# LDOs.net
KiCad netlist of a schematic drawn in Altium Designer
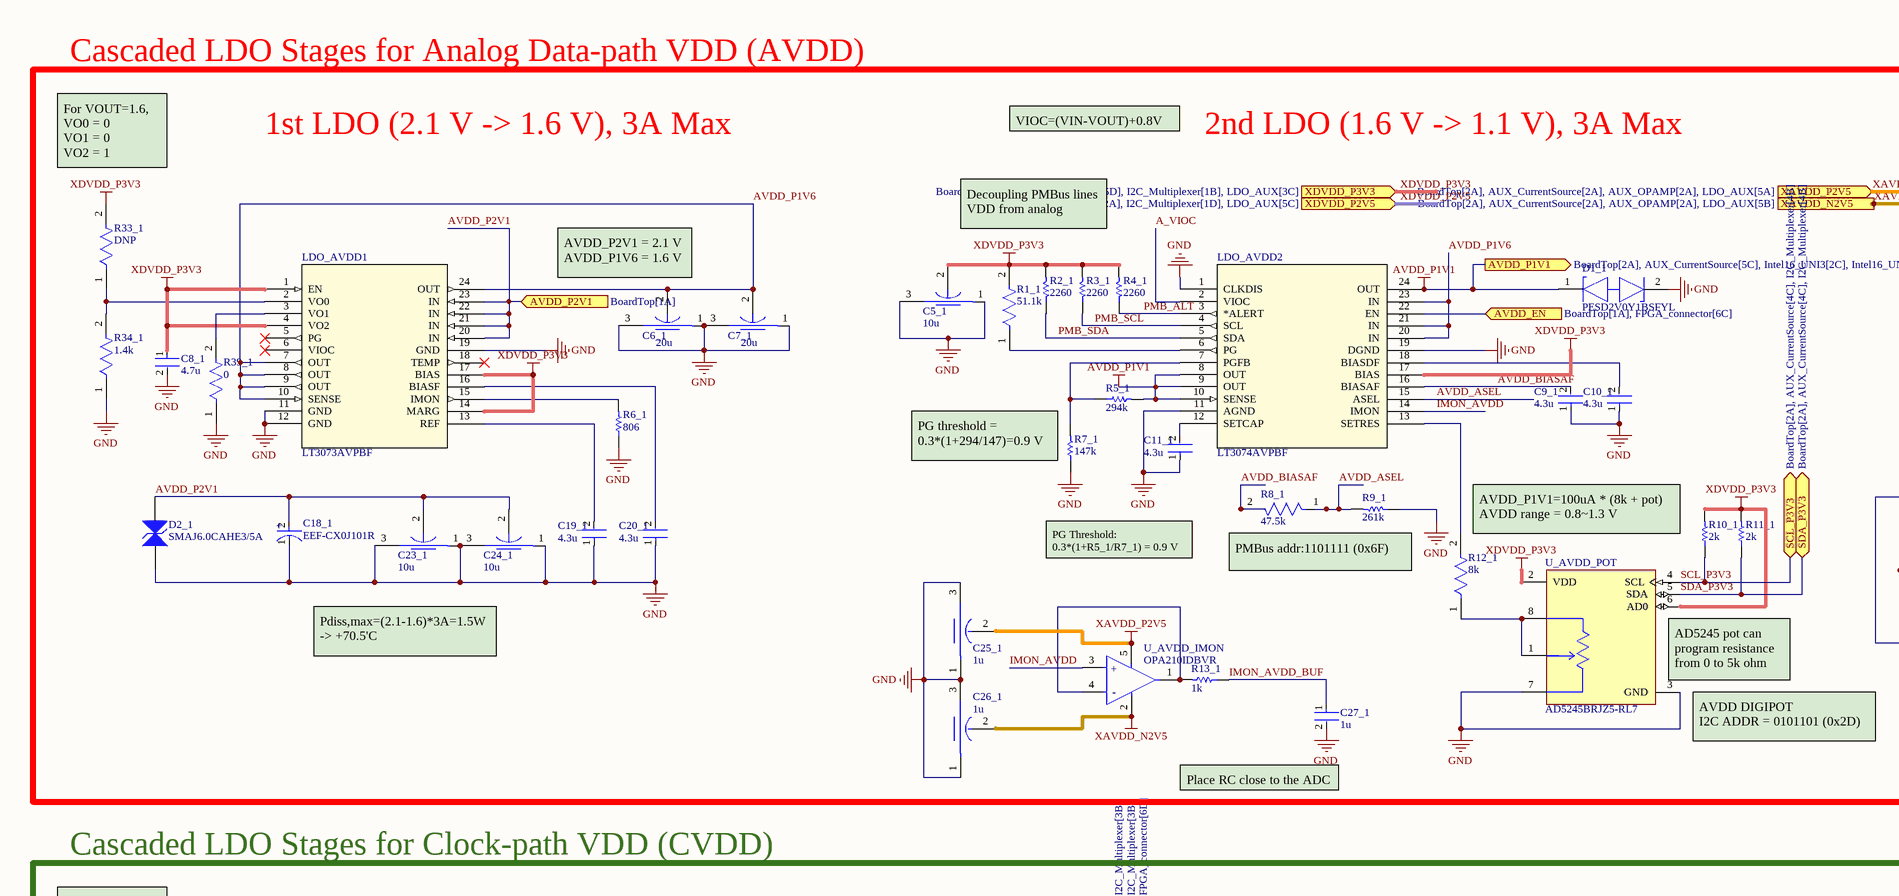
[diagram p0: LDOs.SchDoc, top left]
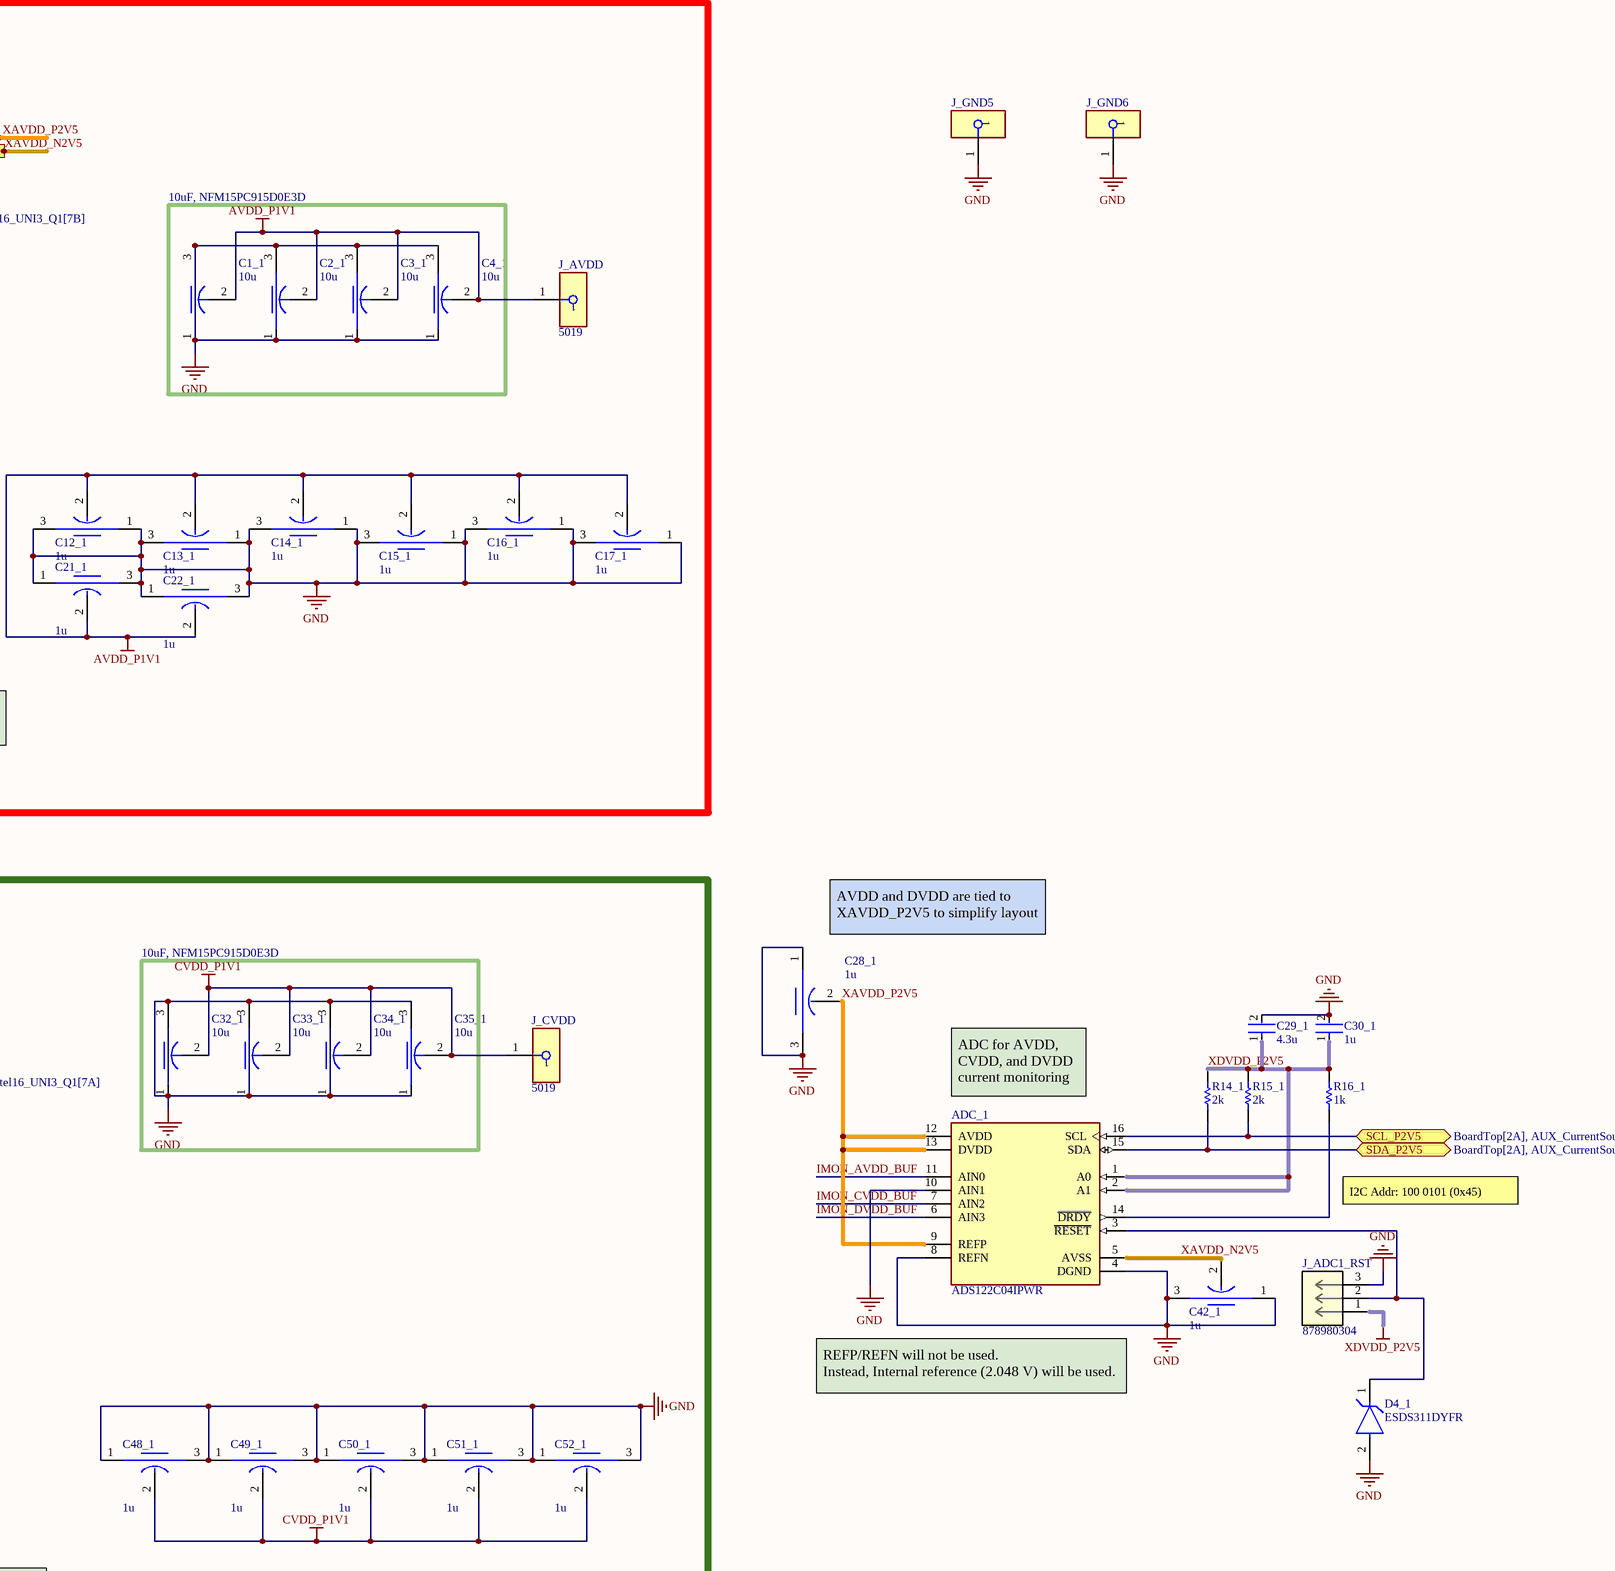
[diagram p1: LDOs.SchDoc, top right]
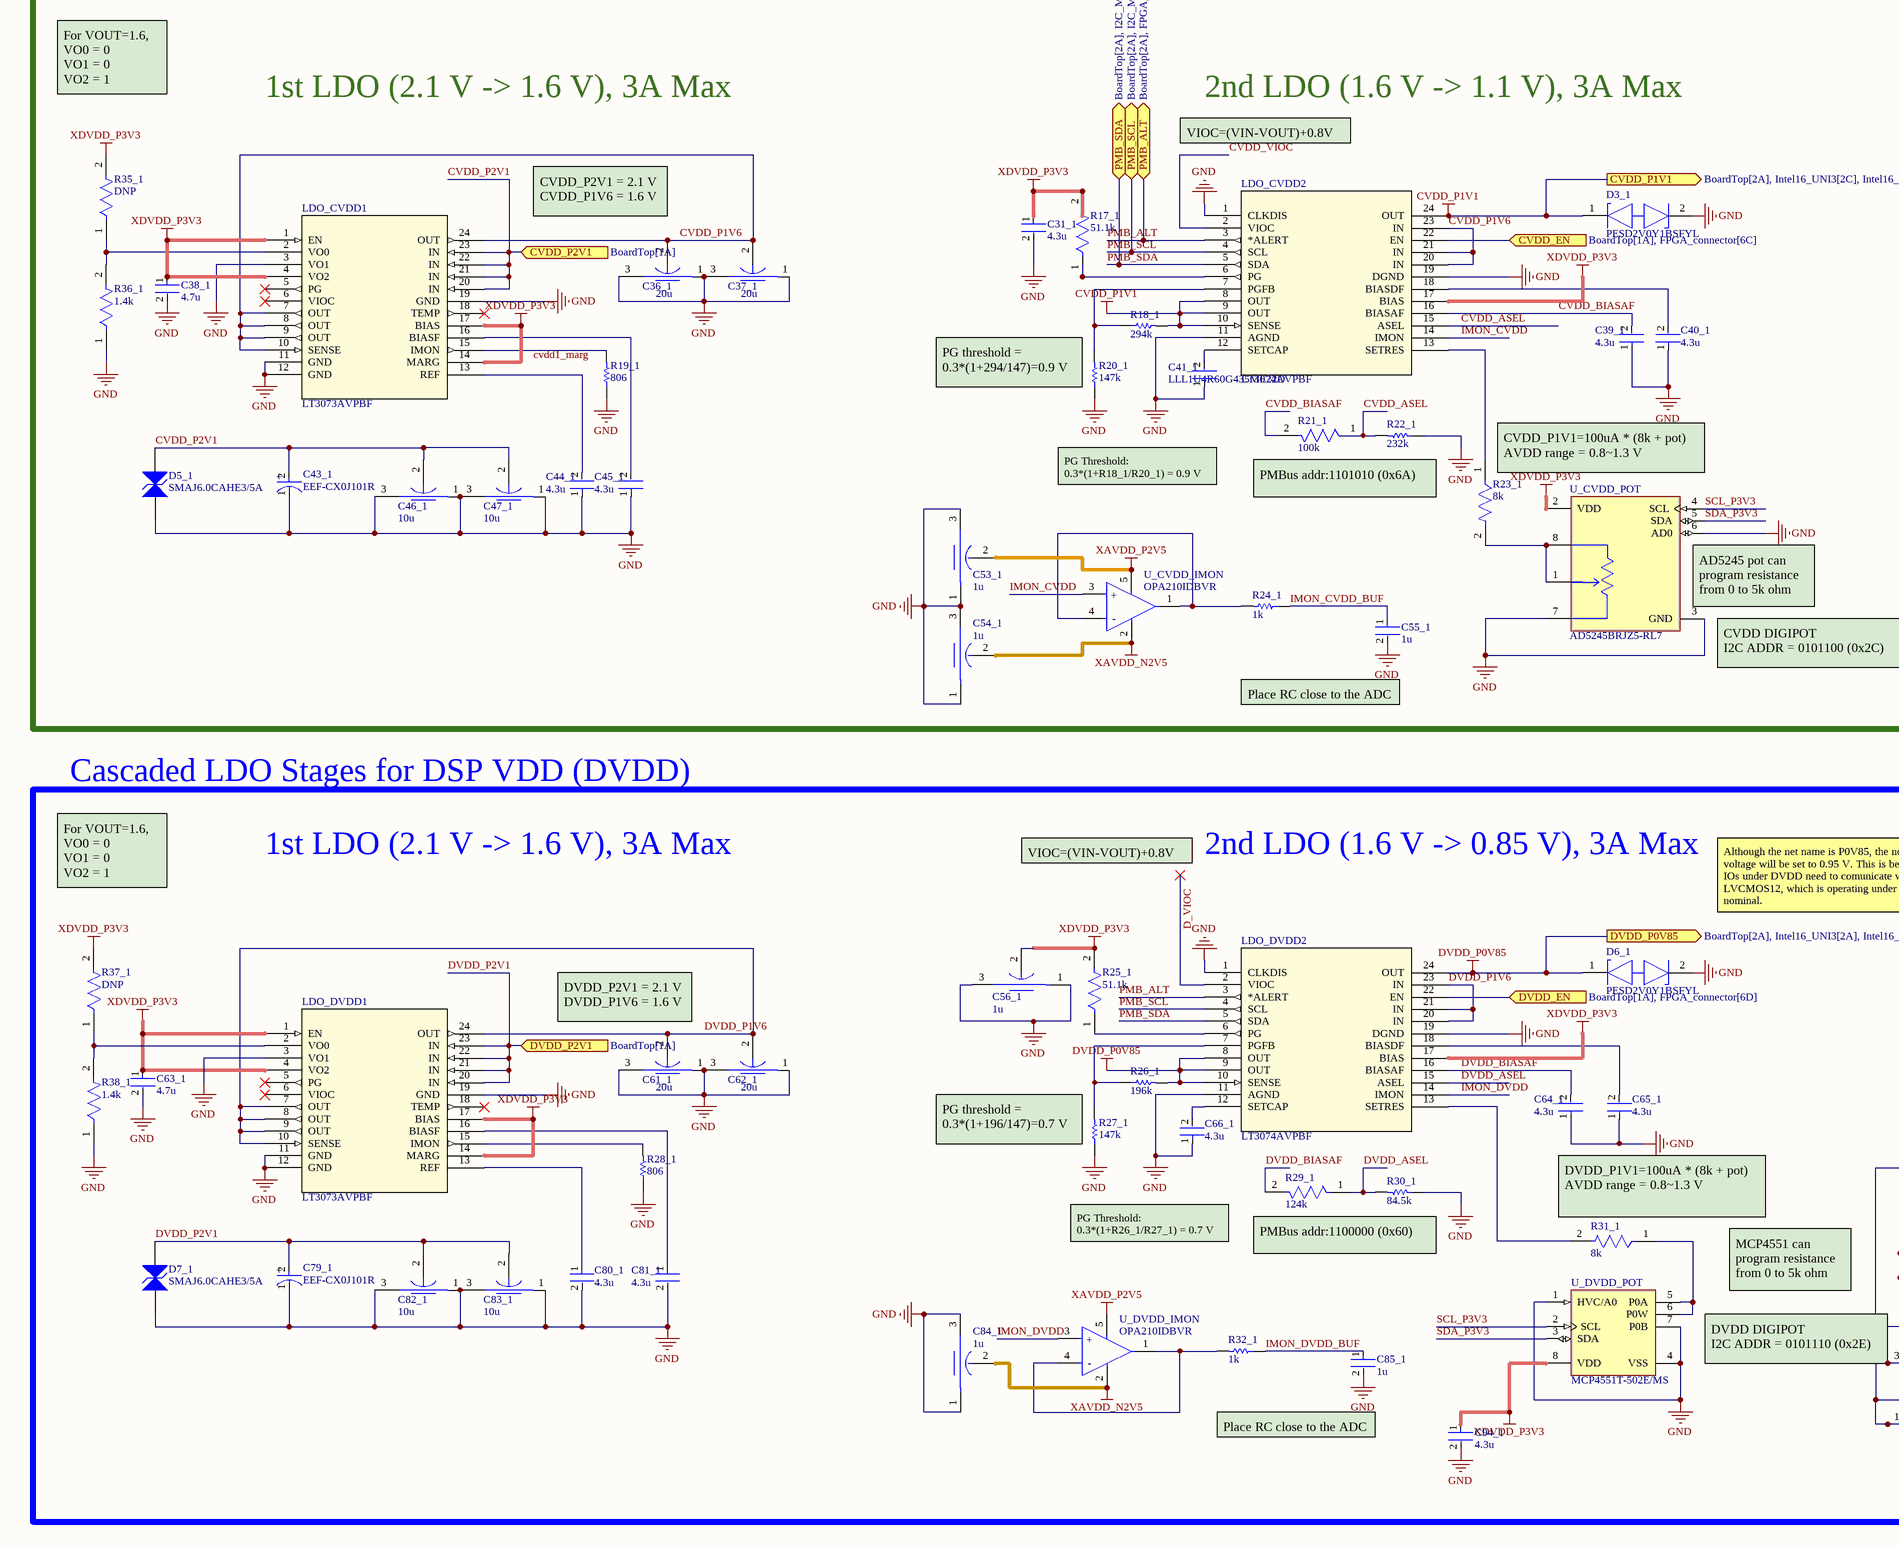
[diagram p2: LDOs.SchDoc, bottom left]
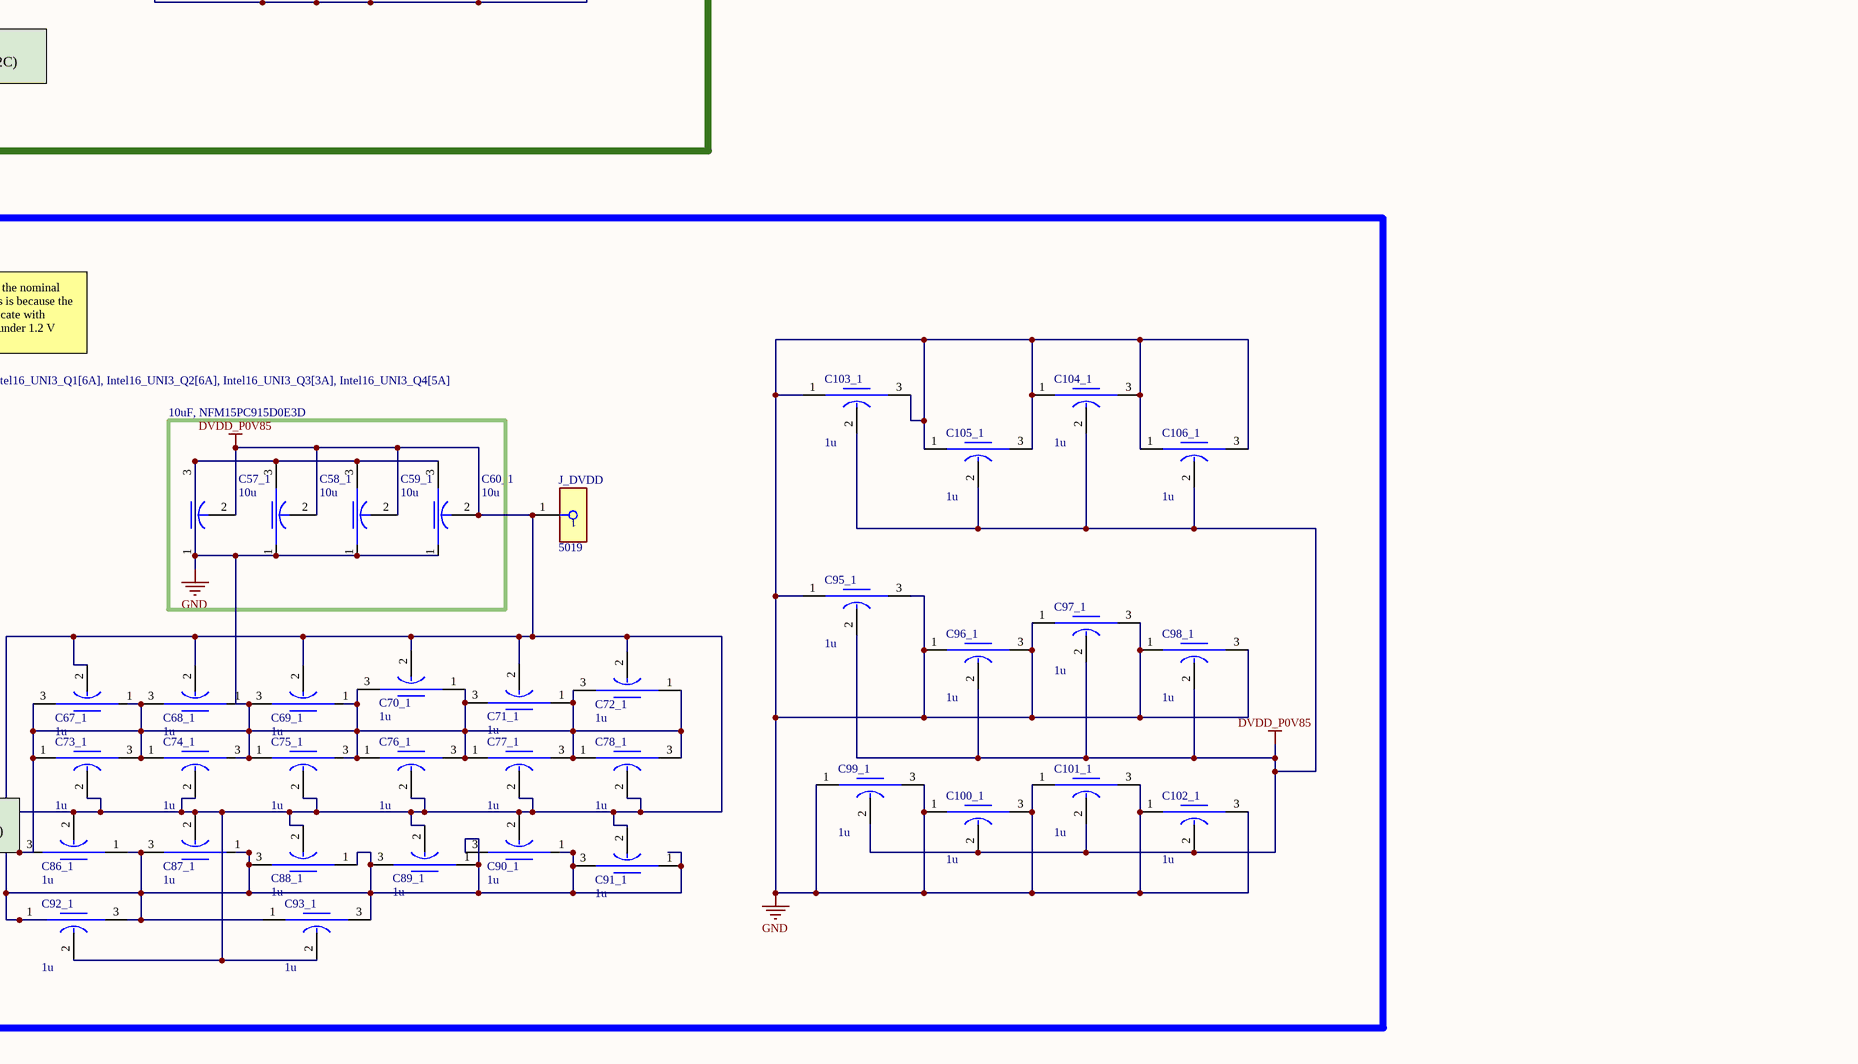
[diagram p3: LDOs.SchDoc, bottom right]

(export (version "E")
  (design (tool "Eeschema 10.0.6"))
  (components
    (comp (ref "ADC_1")
      (value "ADS122C04IPWR")
      (footprint "FP-PW0016A-IPC_C")
      (description "IC ADC 24BIT SIGMA-DELTA 16TSSOP")
      (libsource (lib "Altium Content Vault") (part "c28109da439a1fe3ed8269d84f6cd58"))
    )
    (comp (ref "C1_1")
      (value "10u")
      (footprint "FP-NFM15-0_2-MFG")
      (description "CAP FEEDTHRU")
      (libsource (lib "Altium Content Vault") (part "0d6e7657c98936515f4dd3c3b322889"))
    )
    (comp (ref "C2_1")
      (value "10u")
      (footprint "FP-NFM15-0_2-MFG")
      (description "CAP FEEDTHRU")
      (libsource (lib "Altium Content Vault") (part "0d6e7657c98936515f4dd3c3b322889"))
    )
    (comp (ref "C3_1")
      (value "10u")
      (footprint "FP-NFM15-0_2-MFG")
      (description "CAP FEEDTHRU")
      (libsource (lib "Altium Content Vault") (part "0d6e7657c98936515f4dd3c3b322889"))
    )
    (comp (ref "C4_1")
      (value "10u")
      (footprint "FP-NFM15-0_2-MFG")
      (description "CAP FEEDTHRU")
      (libsource (lib "Altium Content Vault") (part "0d6e7657c98936515f4dd3c3b322889"))
    )
    (comp (ref "C5_1")
      (value "10u")
      (footprint "FP-NFM15-0_2-MFG")
      (description "CAP FEEDTHRU")
      (libsource (lib "Altium Content Vault") (part "0d6e7657c98936515f4dd3c3b322889"))
    )
    (comp (ref "C6_1")
      (value "20u")
      (footprint "FP-NFM15-0_2-MFG")
      (description "CAP FEEDTHRU")
      (libsource (lib "Altium Content Vault") (part "0d6e7657c98936515f4dd3c3b322889"))
    )
    (comp (ref "C7_1")
      (value "20u")
      (footprint "FP-NFM15-0_2-MFG")
      (description "CAP FEEDTHRU")
      (libsource (lib "Altium Content Vault") (part "0d6e7657c98936515f4dd3c3b322889"))
    )
    (comp (ref "C8_1")
      (value "4.7u")
      (footprint "FP-GRM155-0_1-IPC_B")
      (description "Chip Multilayer Ceramic Capacitors for General Purpose, 0402, 4.7uF, X5R, 15%, 20%, 6.3V")
      (fields (field (name "VOLTAGE") "6.3V") (field (name "TOLERANCE") "20%"))
      (libsource (lib "Altium Content Vault") (part "11868f565c42a9108669ba33697ecf6"))
    )
    (comp (ref "C9_1")
      (value "4.3u")
      (footprint "FP-LLL1U4-0_05-IPC_C")
      (description "Cap Ceramic Monolithic 4.3uF 20% 4V X5R 15% 02404 (0610M)")
      (fields (field (name "TOLERANCE") "20%"))
      (libsource (lib "LLL_cap") (part "CMP-06035-061933-1"))
    )
    (comp (ref "C10_1")
      (value "4.3u")
      (footprint "FP-LLL1U4-0_05-IPC_C")
      (description "Cap Ceramic Monolithic 4.3uF 20% 4V X5R 15% 02404 (0610M)")
      (fields (field (name "TOLERANCE") "20%"))
      (libsource (lib "LLL_cap") (part "CMP-06035-061933-1"))
    )
    (comp (ref "C11_1")
      (value "4.3u")
      (footprint "FP-LLL1U4-0_05-IPC_C")
      (description "Cap Ceramic Monolithic 4.3uF 20% 4V X5R 15% 02404 (0610M)")
      (fields (field (name "TOLERANCE") "20%"))
      (libsource (lib "LLL_cap") (part "CMP-06035-061933-1"))
    )
    (comp (ref "C12_1")
      (value "1u")
      (footprint "PCBComponent_1")
      (description "0402(1005M) 4V 1.0UF +/- 20% 3 T")
      (fields (field (name "TOLERANCE") "20%"))
      (libsource (lib "NFM15HC105D0G3D") (part "CMP-06053-000757-1"))
    )
    (comp (ref "C13_1")
      (value "1u")
      (footprint "PCBComponent_1")
      (description "0402(1005M) 4V 1.0UF +/- 20% 3 T")
      (fields (field (name "TOLERANCE") "20%"))
      (libsource (lib "NFM15HC105D0G3D") (part "CMP-06053-000757-1"))
    )
    (comp (ref "C14_1")
      (value "1u")
      (footprint "PCBComponent_1")
      (description "0402(1005M) 4V 1.0UF +/- 20% 3 T")
      (fields (field (name "TOLERANCE") "20%"))
      (libsource (lib "NFM15HC105D0G3D") (part "CMP-06053-000757-1"))
    )
    (comp (ref "C15_1")
      (value "1u")
      (footprint "PCBComponent_1")
      (description "0402(1005M) 4V 1.0UF +/- 20% 3 T")
      (fields (field (name "TOLERANCE") "20%"))
      (libsource (lib "NFM15HC105D0G3D") (part "CMP-06053-000757-1"))
    )
    (comp (ref "C16_1")
      (value "1u")
      (footprint "PCBComponent_1")
      (description "0402(1005M) 4V 1.0UF +/- 20% 3 T")
      (fields (field (name "TOLERANCE") "20%"))
      (libsource (lib "NFM15HC105D0G3D") (part "CMP-06053-000757-1"))
    )
    (comp (ref "C17_1")
      (value "1u")
      (footprint "PCBComponent_1")
      (description "0402(1005M) 4V 1.0UF +/- 20% 3 T")
      (fields (field (name "TOLERANCE") "20%"))
      (libsource (lib "NFM15HC105D0G3D") (part "CMP-06053-000757-1"))
    )
    (comp (ref "C18_1")
      (value "EEF-CX0J101R")
      (footprint "FP-CX-MFG")
      (description "CAP ALUM POLY 100UF 20% 6.3V SMD")
      (fields (field (name "VOLTAGE") "6.3V") (field (name "TOLERANCE") "20%"))
      (libsource (lib "Altium Content Vault") (part "a00bbbee19879c290e62620ae7e47b1"))
    )
    (comp (ref "C19_1")
      (value "4.3u")
      (footprint "FP-LLL1U4-0_05-IPC_C")
      (description "Cap Ceramic Monolithic 4.3uF 20% 4V X5R 15% 02404 (0610M)")
      (fields (field (name "TOLERANCE") "20%"))
      (libsource (lib "LLL_cap") (part "CMP-06035-061933-1"))
    )
    (comp (ref "C20_1")
      (value "4.3u")
      (footprint "FP-LLL1U4-0_05-IPC_C")
      (description "Cap Ceramic Monolithic 4.3uF 20% 4V X5R 15% 02404 (0610M)")
      (fields (field (name "TOLERANCE") "20%"))
      (libsource (lib "LLL_cap") (part "CMP-06035-061933-1"))
    )
    (comp (ref "C21_1")
      (value "1u")
      (footprint "PCBComponent_1")
      (description "0402(1005M) 4V 1.0UF +/- 20% 3 T")
      (fields (field (name "TOLERANCE") "20%"))
      (libsource (lib "NFM15HC105D0G3D") (part "CMP-06053-000757-1"))
    )
    (comp (ref "C22_1")
      (value "1u")
      (footprint "PCBComponent_1")
      (description "0402(1005M) 4V 1.0UF +/- 20% 3 T")
      (fields (field (name "TOLERANCE") "20%"))
      (libsource (lib "NFM15HC105D0G3D") (part "CMP-06053-000757-1"))
    )
    (comp (ref "C23_1")
      (value "10u")
      (footprint "FP-NFM15-0_2-MFG")
      (description "CAP FEEDTHRU")
      (libsource (lib "Altium Content Vault") (part "0d6e7657c98936515f4dd3c3b322889"))
    )
    (comp (ref "C24_1")
      (value "10u")
      (footprint "FP-NFM15-0_2-MFG")
      (description "CAP FEEDTHRU")
      (libsource (lib "Altium Content Vault") (part "0d6e7657c98936515f4dd3c3b322889"))
    )
    (comp (ref "C25_1")
      (value "1u")
      (footprint "PCBComponent_1")
      (description "0402(1005M) 4V 1.0UF +/- 20% 3 T")
      (fields (field (name "TOLERANCE") "20%"))
      (libsource (lib "NFM15HC105D0G3D") (part "CMP-06053-000757-1"))
    )
    (comp (ref "C26_1")
      (value "1u")
      (footprint "PCBComponent_1")
      (description "0402(1005M) 4V 1.0UF +/- 20% 3 T")
      (fields (field (name "TOLERANCE") "20%"))
      (libsource (lib "NFM15HC105D0G3D") (part "CMP-06053-000757-1"))
    )
    (comp (ref "C27_1")
      (value "1u")
      (footprint "FP-C0402C105K8PACTU-IPC_A")
      (description "CAP CER 1UF 10V X5R 0402")
      (fields (field (name "VOLTAGE") "10V") (field (name "TOLERANCE") "10%"))
      (libsource (lib "KEMET_1uF_0402_cap") (part "CMP-2008-02081-2"))
    )
    (comp (ref "C28_1")
      (value "1u")
      (footprint "PCBComponent_1")
      (description "0402(1005M) 4V 1.0UF +/- 20% 3 T")
      (fields (field (name "TOLERANCE") "20%"))
      (libsource (lib "NFM15HC105D0G3D") (part "CMP-06053-000757-1"))
    )
    (comp (ref "C29_1")
      (value "4.3u")
      (footprint "FP-LLL1U4-0_05-MFG")
      (description "Cap Ceramic Monolithic 4.3uF 20% 4V X5R 15% 02404 (0610M)")
      (fields (field (name "TOLERANCE") "20%"))
      (libsource (lib "Altium Content Vault") (part "b4654b650e69147ec39a6b967a45e02"))
    )
    (comp (ref "C30_1")
      (value "1u")
      (footprint "FP-C0402C105K8PACTU-IPC_A")
      (description "CAP CER 1UF 10V X5R 0402")
      (fields (field (name "VOLTAGE") "10V") (field (name "TOLERANCE") "10%"))
      (libsource (lib "KEMET_1uF_0402_cap") (part "CMP-2008-02081-2"))
    )
    (comp (ref "C31_1")
      (value "4.3u")
      (footprint "FP-LLL1U4-0_05-IPC_C")
      (description "Cap Ceramic Monolithic 4.3uF 20% 4V X5R 15% 02404 (0610M)")
      (fields (field (name "TOLERANCE") "20%"))
      (libsource (lib "LLL_cap") (part "CMP-06035-061933-1"))
    )
    (comp (ref "C32_1")
      (value "10u")
      (footprint "FP-NFM15-0_2-MFG")
      (description "CAP FEEDTHRU")
      (libsource (lib "Altium Content Vault") (part "0d6e7657c98936515f4dd3c3b322889"))
    )
    (comp (ref "C33_1")
      (value "10u")
      (footprint "FP-NFM15-0_2-MFG")
      (description "CAP FEEDTHRU")
      (libsource (lib "Altium Content Vault") (part "0d6e7657c98936515f4dd3c3b322889"))
    )
    (comp (ref "C34_1")
      (value "10u")
      (footprint "FP-NFM15-0_2-MFG")
      (description "CAP FEEDTHRU")
      (libsource (lib "Altium Content Vault") (part "0d6e7657c98936515f4dd3c3b322889"))
    )
    (comp (ref "C35_1")
      (value "10u")
      (footprint "FP-NFM15-0_2-MFG")
      (description "CAP FEEDTHRU")
      (libsource (lib "Altium Content Vault") (part "0d6e7657c98936515f4dd3c3b322889"))
    )
    (comp (ref "C36_1")
      (value "20u")
      (footprint "FP-NFM15-0_2-MFG")
      (description "CAP FEEDTHRU")
      (libsource (lib "Altium Content Vault") (part "0d6e7657c98936515f4dd3c3b322889"))
    )
    (comp (ref "C37_1")
      (value "20u")
      (footprint "FP-NFM15-0_2-MFG")
      (description "CAP FEEDTHRU")
      (libsource (lib "Altium Content Vault") (part "0d6e7657c98936515f4dd3c3b322889"))
    )
    (comp (ref "C38_1")
      (value "4.7u")
      (footprint "FP-GRM155-0_1-IPC_B")
      (description "Chip Multilayer Ceramic Capacitors for General Purpose, 0402, 4.7uF, X5R, 15%, 20%, 6.3V")
      (fields (field (name "VOLTAGE") "6.3V") (field (name "TOLERANCE") "20%"))
      (libsource (lib "Altium Content Vault") (part "11868f565c42a9108669ba33697ecf6"))
    )
    (comp (ref "C39_1")
      (value "4.3u")
      (footprint "FP-LLL1U4-0_05-IPC_C")
      (description "Cap Ceramic Monolithic 4.3uF 20% 4V X5R 15% 02404 (0610M)")
      (fields (field (name "TOLERANCE") "20%"))
      (libsource (lib "LLL_cap") (part "CMP-06035-061933-1"))
    )
    (comp (ref "C40_1")
      (value "4.3u")
      (footprint "FP-LLL1U4-0_05-IPC_C")
      (description "Cap Ceramic Monolithic 4.3uF 20% 4V X5R 15% 02404 (0610M)")
      (fields (field (name "TOLERANCE") "20%"))
      (libsource (lib "LLL_cap") (part "CMP-06035-061933-1"))
    )
    (comp (ref "C41_1")
      (value "LLL1U4R60G435ME22D")
      (footprint "FP-LLL1U4-0_05-IPC_C")
      (description "Cap Ceramic Monolithic 4.3uF 20% 4V X5R 15% 02404 (0610M)")
      (fields (field (name "TOLERANCE") "20%"))
      (libsource (lib "LLL_cap") (part "CMP-06035-061933-1"))
    )
    (comp (ref "C42_1")
      (value "1u")
      (footprint "PCBComponent_1")
      (description "0402(1005M) 4V 1.0UF +/- 20% 3 T")
      (fields (field (name "TOLERANCE") "20%"))
      (libsource (lib "NFM15HC105D0G3D") (part "CMP-06053-000757-1"))
    )
    (comp (ref "C43_1")
      (value "EEF-CX0J101R")
      (footprint "FP-CX-MFG")
      (description "CAP ALUM POLY 100UF 20% 6.3V SMD")
      (fields (field (name "VOLTAGE") "6.3V") (field (name "TOLERANCE") "20%"))
      (libsource (lib "Altium Content Vault") (part "a00bbbee19879c290e62620ae7e47b1"))
    )
    (comp (ref "C44_1")
      (value "4.3u")
      (footprint "FP-LLL1U4-0_05-IPC_C")
      (description "Cap Ceramic Monolithic 4.3uF 20% 4V X5R 15% 02404 (0610M)")
      (fields (field (name "TOLERANCE") "20%"))
      (libsource (lib "LLL_cap") (part "CMP-06035-061933-1"))
    )
    (comp (ref "C45_1")
      (value "4.3u")
      (footprint "FP-LLL1U4-0_05-IPC_C")
      (description "Cap Ceramic Monolithic 4.3uF 20% 4V X5R 15% 02404 (0610M)")
      (fields (field (name "TOLERANCE") "20%"))
      (libsource (lib "LLL_cap") (part "CMP-06035-061933-1"))
    )
    (comp (ref "C46_1")
      (value "10u")
      (footprint "FP-NFM15-0_2-MFG")
      (description "CAP FEEDTHRU")
      (libsource (lib "Altium Content Vault") (part "0d6e7657c98936515f4dd3c3b322889"))
    )
    (comp (ref "C47_1")
      (value "10u")
      (footprint "FP-NFM15-0_2-MFG")
      (description "CAP FEEDTHRU")
      (libsource (lib "Altium Content Vault") (part "0d6e7657c98936515f4dd3c3b322889"))
    )
    (comp (ref "C48_1")
      (value "1u")
      (footprint "PCBComponent_1")
      (description "0402(1005M) 4V 1.0UF +/- 20% 3 T")
      (fields (field (name "TOLERANCE") "20%"))
      (libsource (lib "NFM15HC105D0G3D") (part "CMP-06053-000757-1"))
    )
    (comp (ref "C49_1")
      (value "1u")
      (footprint "PCBComponent_1")
      (description "0402(1005M) 4V 1.0UF +/- 20% 3 T")
      (fields (field (name "TOLERANCE") "20%"))
      (libsource (lib "NFM15HC105D0G3D") (part "CMP-06053-000757-1"))
    )
    (comp (ref "C50_1")
      (value "1u")
      (footprint "PCBComponent_1")
      (description "0402(1005M) 4V 1.0UF +/- 20% 3 T")
      (fields (field (name "TOLERANCE") "20%"))
      (libsource (lib "NFM15HC105D0G3D") (part "CMP-06053-000757-1"))
    )
    (comp (ref "C51_1")
      (value "1u")
      (footprint "PCBComponent_1")
      (description "0402(1005M) 4V 1.0UF +/- 20% 3 T")
      (fields (field (name "TOLERANCE") "20%"))
      (libsource (lib "NFM15HC105D0G3D") (part "CMP-06053-000757-1"))
    )
    (comp (ref "C52_1")
      (value "1u")
      (footprint "PCBComponent_1")
      (description "0402(1005M) 4V 1.0UF +/- 20% 3 T")
      (fields (field (name "TOLERANCE") "20%"))
      (libsource (lib "NFM15HC105D0G3D") (part "CMP-06053-000757-1"))
    )
    (comp (ref "C53_1")
      (value "1u")
      (footprint "PCBComponent_1")
      (description "0402(1005M) 4V 1.0UF +/- 20% 3 T")
      (fields (field (name "TOLERANCE") "20%"))
      (libsource (lib "NFM15HC105D0G3D") (part "CMP-06053-000757-1"))
    )
    (comp (ref "C54_1")
      (value "1u")
      (footprint "PCBComponent_1")
      (description "0402(1005M) 4V 1.0UF +/- 20% 3 T")
      (fields (field (name "TOLERANCE") "20%"))
      (libsource (lib "NFM15HC105D0G3D") (part "CMP-06053-000757-1"))
    )
    (comp (ref "C55_1")
      (value "1u")
      (footprint "FP-C0402C105K8PACTU-IPC_A")
      (description "CAP CER 1UF 10V X5R 0402")
      (fields (field (name "VOLTAGE") "10V") (field (name "TOLERANCE") "10%"))
      (libsource (lib "KEMET_1uF_0402_cap") (part "CMP-2008-02081-2"))
    )
    (comp (ref "C56_1")
      (value "1u")
      (footprint "PCBComponent_1")
      (description "0402(1005M) 4V 1.0UF +/- 20% 3 T")
      (fields (field (name "TOLERANCE") "20%"))
      (libsource (lib "NFM15HC105D0G3D") (part "CMP-06053-000757-1"))
    )
    (comp (ref "C57_1")
      (value "10u")
      (footprint "FP-NFM15-0_2-MFG")
      (description "CAP FEEDTHRU")
      (libsource (lib "Altium Content Vault") (part "0d6e7657c98936515f4dd3c3b322889"))
    )
    (comp (ref "C58_1")
      (value "10u")
      (footprint "FP-NFM15-0_2-MFG")
      (description "CAP FEEDTHRU")
      (libsource (lib "Altium Content Vault") (part "0d6e7657c98936515f4dd3c3b322889"))
    )
    (comp (ref "C59_1")
      (value "10u")
      (footprint "FP-NFM15-0_2-MFG")
      (description "CAP FEEDTHRU")
      (libsource (lib "Altium Content Vault") (part "0d6e7657c98936515f4dd3c3b322889"))
    )
    (comp (ref "C60_1")
      (value "10u")
      (footprint "FP-NFM15-0_2-MFG")
      (description "CAP FEEDTHRU")
      (libsource (lib "Altium Content Vault") (part "0d6e7657c98936515f4dd3c3b322889"))
    )
    (comp (ref "C61_1")
      (value "20u")
      (footprint "FP-NFM15-0_2-MFG")
      (description "CAP FEEDTHRU")
      (libsource (lib "Altium Content Vault") (part "0d6e7657c98936515f4dd3c3b322889"))
    )
    (comp (ref "C62_1")
      (value "20u")
      (footprint "FP-NFM15-0_2-MFG")
      (description "CAP FEEDTHRU")
      (libsource (lib "Altium Content Vault") (part "0d6e7657c98936515f4dd3c3b322889"))
    )
    (comp (ref "C63_1")
      (value "4.7u")
      (footprint "FP-GRM155-0_1-IPC_B")
      (description "Chip Multilayer Ceramic Capacitors for General Purpose, 0402, 4.7uF, X5R, 15%, 20%, 6.3V")
      (fields (field (name "VOLTAGE") "6.3V") (field (name "TOLERANCE") "20%"))
      (libsource (lib "Altium Content Vault") (part "11868f565c42a9108669ba33697ecf6"))
    )
    (comp (ref "C64_1")
      (value "4.3u")
      (footprint "FP-LLL1U4-0_05-IPC_C")
      (description "Cap Ceramic Monolithic 4.3uF 20% 4V X5R 15% 02404 (0610M)")
      (fields (field (name "TOLERANCE") "20%"))
      (libsource (lib "LLL_cap") (part "CMP-06035-061933-1"))
    )
    (comp (ref "C65_1")
      (value "4.3u")
      (footprint "FP-LLL1U4-0_05-IPC_C")
      (description "Cap Ceramic Monolithic 4.3uF 20% 4V X5R 15% 02404 (0610M)")
      (fields (field (name "TOLERANCE") "20%"))
      (libsource (lib "LLL_cap") (part "CMP-06035-061933-1"))
    )
    (comp (ref "C66_1")
      (value "4.3u")
      (footprint "FP-LLL1U4-0_05-IPC_C")
      (description "Cap Ceramic Monolithic 4.3uF 20% 4V X5R 15% 02404 (0610M)")
      (fields (field (name "TOLERANCE") "20%"))
      (libsource (lib "LLL_cap") (part "CMP-06035-061933-1"))
    )
    (comp (ref "C67_1")
      (value "1u")
      (footprint "PCBComponent_1")
      (description "0402(1005M) 4V 1.0UF +/- 20% 3 T")
      (fields (field (name "TOLERANCE") "20%"))
      (libsource (lib "NFM15HC105D0G3D") (part "CMP-06053-000757-1"))
    )
    (comp (ref "C68_1")
      (value "1u")
      (footprint "PCBComponent_1")
      (description "0402(1005M) 4V 1.0UF +/- 20% 3 T")
      (fields (field (name "TOLERANCE") "20%"))
      (libsource (lib "NFM15HC105D0G3D") (part "CMP-06053-000757-1"))
    )
    (comp (ref "C69_1")
      (value "1u")
      (footprint "PCBComponent_1")
      (description "0402(1005M) 4V 1.0UF +/- 20% 3 T")
      (fields (field (name "TOLERANCE") "20%"))
      (libsource (lib "NFM15HC105D0G3D") (part "CMP-06053-000757-1"))
    )
    (comp (ref "C70_1")
      (value "1u")
      (footprint "PCBComponent_1")
      (description "0402(1005M) 4V 1.0UF +/- 20% 3 T")
      (fields (field (name "TOLERANCE") "20%"))
      (libsource (lib "NFM15HC105D0G3D") (part "CMP-06053-000757-1"))
    )
    (comp (ref "C71_1")
      (value "1u")
      (footprint "PCBComponent_1")
      (description "0402(1005M) 4V 1.0UF +/- 20% 3 T")
      (fields (field (name "TOLERANCE") "20%"))
      (libsource (lib "NFM15HC105D0G3D") (part "CMP-06053-000757-1"))
    )
    (comp (ref "C72_1")
      (value "1u")
      (footprint "PCBComponent_1")
      (description "0402(1005M) 4V 1.0UF +/- 20% 3 T")
      (fields (field (name "TOLERANCE") "20%"))
      (libsource (lib "NFM15HC105D0G3D") (part "CMP-06053-000757-1"))
    )
    (comp (ref "C73_1")
      (value "1u")
      (footprint "PCBComponent_1")
      (description "0402(1005M) 4V 1.0UF +/- 20% 3 T")
      (fields (field (name "TOLERANCE") "20%"))
      (libsource (lib "NFM15HC105D0G3D") (part "CMP-06053-000757-1"))
    )
    (comp (ref "C74_1")
      (value "1u")
      (footprint "PCBComponent_1")
      (description "0402(1005M) 4V 1.0UF +/- 20% 3 T")
      (fields (field (name "TOLERANCE") "20%"))
      (libsource (lib "NFM15HC105D0G3D") (part "CMP-06053-000757-1"))
    )
    (comp (ref "C75_1")
      (value "1u")
      (footprint "PCBComponent_1")
      (description "0402(1005M) 4V 1.0UF +/- 20% 3 T")
      (fields (field (name "TOLERANCE") "20%"))
      (libsource (lib "NFM15HC105D0G3D") (part "CMP-06053-000757-1"))
    )
    (comp (ref "C76_1")
      (value "1u")
      (footprint "PCBComponent_1")
      (description "0402(1005M) 4V 1.0UF +/- 20% 3 T")
      (fields (field (name "TOLERANCE") "20%"))
      (libsource (lib "NFM15HC105D0G3D") (part "CMP-06053-000757-1"))
    )
    (comp (ref "C77_1")
      (value "1u")
      (footprint "PCBComponent_1")
      (description "0402(1005M) 4V 1.0UF +/- 20% 3 T")
      (fields (field (name "TOLERANCE") "20%"))
      (libsource (lib "NFM15HC105D0G3D") (part "CMP-06053-000757-1"))
    )
    (comp (ref "C78_1")
      (value "1u")
      (footprint "PCBComponent_1")
      (description "0402(1005M) 4V 1.0UF +/- 20% 3 T")
      (fields (field (name "TOLERANCE") "20%"))
      (libsource (lib "NFM15HC105D0G3D") (part "CMP-06053-000757-1"))
    )
    (comp (ref "C79_1")
      (value "EEF-CX0J101R")
      (footprint "FP-CX-MFG")
      (description "CAP ALUM POLY 100UF 20% 6.3V SMD")
      (fields (field (name "VOLTAGE") "6.3V") (field (name "TOLERANCE") "20%"))
      (libsource (lib "Altium Content Vault") (part "a00bbbee19879c290e62620ae7e47b1"))
    )
    (comp (ref "C80_1")
      (value "4.3u")
      (footprint "FP-LLL1U4-0_05-IPC_C")
      (description "Cap Ceramic Monolithic 4.3uF 20% 4V X5R 15% 02404 (0610M)")
      (fields (field (name "TOLERANCE") "20%"))
      (libsource (lib "LLL_cap") (part "CMP-06035-061933-1"))
    )
    (comp (ref "C81_1")
      (value "4.3u")
      (footprint "FP-LLL1U4-0_05-IPC_C")
      (description "Cap Ceramic Monolithic 4.3uF 20% 4V X5R 15% 02404 (0610M)")
      (fields (field (name "TOLERANCE") "20%"))
      (libsource (lib "LLL_cap") (part "CMP-06035-061933-1"))
    )
    (comp (ref "C82_1")
      (value "10u")
      (footprint "FP-NFM15-0_2-MFG")
      (description "CAP FEEDTHRU")
      (libsource (lib "Altium Content Vault") (part "0d6e7657c98936515f4dd3c3b322889"))
    )
    (comp (ref "C83_1")
      (value "10u")
      (footprint "FP-NFM15-0_2-MFG")
      (description "CAP FEEDTHRU")
      (libsource (lib "Altium Content Vault") (part "0d6e7657c98936515f4dd3c3b322889"))
    )
    (comp (ref "C84_1")
      (value "1u")
      (footprint "PCBComponent_1")
      (description "0402(1005M) 4V 1.0UF +/- 20% 3 T")
      (fields (field (name "TOLERANCE") "20%"))
      (libsource (lib "NFM15HC105D0G3D") (part "CMP-06053-000757-1"))
    )
    (comp (ref "C85_1")
      (value "1u")
      (footprint "FP-C0402C105K8PACTU-IPC_A")
      (description "CAP CER 1UF 10V X5R 0402")
      (fields (field (name "VOLTAGE") "10V") (field (name "TOLERANCE") "10%"))
      (libsource (lib "KEMET_1uF_0402_cap") (part "CMP-2008-02081-2"))
    )
    (comp (ref "C86_1")
      (value "1u")
      (footprint "PCBComponent_1")
      (description "0402(1005M) 4V 1.0UF +/- 20% 3 T")
      (fields (field (name "TOLERANCE") "20%"))
      (libsource (lib "NFM15HC105D0G3D") (part "CMP-06053-000757-1"))
    )
    (comp (ref "C87_1")
      (value "1u")
      (footprint "PCBComponent_1")
      (description "0402(1005M) 4V 1.0UF +/- 20% 3 T")
      (fields (field (name "TOLERANCE") "20%"))
      (libsource (lib "NFM15HC105D0G3D") (part "CMP-06053-000757-1"))
    )
    (comp (ref "C88_1")
      (value "1u")
      (footprint "PCBComponent_1")
      (description "0402(1005M) 4V 1.0UF +/- 20% 3 T")
      (fields (field (name "TOLERANCE") "20%"))
      (libsource (lib "NFM15HC105D0G3D") (part "CMP-06053-000757-1"))
    )
    (comp (ref "C89_1")
      (value "1u")
      (footprint "PCBComponent_1")
      (description "0402(1005M) 4V 1.0UF +/- 20% 3 T")
      (fields (field (name "TOLERANCE") "20%"))
      (libsource (lib "NFM15HC105D0G3D") (part "CMP-06053-000757-1"))
    )
    (comp (ref "C90_1")
      (value "1u")
      (footprint "PCBComponent_1")
      (description "0402(1005M) 4V 1.0UF +/- 20% 3 T")
      (fields (field (name "TOLERANCE") "20%"))
      (libsource (lib "NFM15HC105D0G3D") (part "CMP-06053-000757-1"))
    )
    (comp (ref "C91_1")
      (value "1u")
      (footprint "PCBComponent_1")
      (description "0402(1005M) 4V 1.0UF +/- 20% 3 T")
      (fields (field (name "TOLERANCE") "20%"))
      (libsource (lib "NFM15HC105D0G3D") (part "CMP-06053-000757-1"))
    )
    (comp (ref "C92_1")
      (value "1u")
      (footprint "PCBComponent_1")
      (description "0402(1005M) 4V 1.0UF +/- 20% 3 T")
      (fields (field (name "TOLERANCE") "20%"))
      (libsource (lib "NFM15HC105D0G3D") (part "CMP-06053-000757-1"))
    )
    (comp (ref "C93_1")
      (value "1u")
      (footprint "PCBComponent_1")
      (description "0402(1005M) 4V 1.0UF +/- 20% 3 T")
      (fields (field (name "TOLERANCE") "20%"))
      (libsource (lib "NFM15HC105D0G3D") (part "CMP-06053-000757-1"))
    )
    (comp (ref "C94_1")
      (value "4.3u")
      (footprint "FP-LLL1U4-0_05-MFG")
      (description "Cap Ceramic Monolithic 4.3uF 20% 4V X5R 15% 02404 (0610M)")
      (fields (field (name "TOLERANCE") "20%"))
      (libsource (lib "Altium Content Vault") (part "b4654b650e69147ec39a6b967a45e02"))
    )
    (comp (ref "C95_1")
      (value "1u")
      (footprint "PCBComponent_1")
      (description "0402(1005M) 4V 1.0UF +/- 20% 3 T")
      (fields (field (name "TOLERANCE") "20%"))
      (libsource (lib "NFM15HC105D0G3D") (part "CMP-06053-000757-1"))
    )
    (comp (ref "C96_1")
      (value "1u")
      (footprint "PCBComponent_1")
      (description "0402(1005M) 4V 1.0UF +/- 20% 3 T")
      (fields (field (name "TOLERANCE") "20%"))
      (libsource (lib "NFM15HC105D0G3D") (part "CMP-06053-000757-1"))
    )
    (comp (ref "C97_1")
      (value "1u")
      (footprint "PCBComponent_1")
      (description "0402(1005M) 4V 1.0UF +/- 20% 3 T")
      (fields (field (name "TOLERANCE") "20%"))
      (libsource (lib "NFM15HC105D0G3D") (part "CMP-06053-000757-1"))
    )
    (comp (ref "C98_1")
      (value "1u")
      (footprint "PCBComponent_1")
      (description "0402(1005M) 4V 1.0UF +/- 20% 3 T")
      (fields (field (name "TOLERANCE") "20%"))
      (libsource (lib "NFM15HC105D0G3D") (part "CMP-06053-000757-1"))
    )
    (comp (ref "C99_1")
      (value "1u")
      (footprint "PCBComponent_1")
      (description "0402(1005M) 4V 1.0UF +/- 20% 3 T")
      (fields (field (name "TOLERANCE") "20%"))
      (libsource (lib "NFM15HC105D0G3D") (part "CMP-06053-000757-1"))
    )
    (comp (ref "C100_1")
      (value "1u")
      (footprint "PCBComponent_1")
      (description "0402(1005M) 4V 1.0UF +/- 20% 3 T")
      (fields (field (name "TOLERANCE") "20%"))
      (libsource (lib "NFM15HC105D0G3D") (part "CMP-06053-000757-1"))
    )
    (comp (ref "C101_1")
      (value "1u")
      (footprint "PCBComponent_1")
      (description "0402(1005M) 4V 1.0UF +/- 20% 3 T")
      (fields (field (name "TOLERANCE") "20%"))
      (libsource (lib "NFM15HC105D0G3D") (part "CMP-06053-000757-1"))
    )
    (comp (ref "C102_1")
      (value "1u")
      (footprint "PCBComponent_1")
      (description "0402(1005M) 4V 1.0UF +/- 20% 3 T")
      (fields (field (name "TOLERANCE") "20%"))
      (libsource (lib "NFM15HC105D0G3D") (part "CMP-06053-000757-1"))
    )
    (comp (ref "C103_1")
      (value "1u")
      (footprint "PCBComponent_1")
      (description "0402(1005M) 4V 1.0UF +/- 20% 3 T")
      (fields (field (name "TOLERANCE") "20%"))
      (libsource (lib "NFM15HC105D0G3D") (part "CMP-06053-000757-1"))
    )
    (comp (ref "C104_1")
      (value "1u")
      (footprint "PCBComponent_1")
      (description "0402(1005M) 4V 1.0UF +/- 20% 3 T")
      (fields (field (name "TOLERANCE") "20%"))
      (libsource (lib "NFM15HC105D0G3D") (part "CMP-06053-000757-1"))
    )
    (comp (ref "C105_1")
      (value "1u")
      (footprint "PCBComponent_1")
      (description "0402(1005M) 4V 1.0UF +/- 20% 3 T")
      (fields (field (name "TOLERANCE") "20%"))
      (libsource (lib "NFM15HC105D0G3D") (part "CMP-06053-000757-1"))
    )
    (comp (ref "C106_1")
      (value "1u")
      (footprint "PCBComponent_1")
      (description "0402(1005M) 4V 1.0UF +/- 20% 3 T")
      (fields (field (name "TOLERANCE") "20%"))
      (libsource (lib "NFM15HC105D0G3D") (part "CMP-06053-000757-1"))
    )
    (comp (ref "D1_1")
      (value "PESD2V0Y1BSFYL")
      (footprint "FP-SOD962-2-MFG")
      (description "TVS DIODE 2VWM 3VC DSN0603-2")
      (libsource (lib "Altium Content Vault") (part "3b819f4016a974b32db02c4901e5706"))
    )
    (comp (ref "D2_1")
      (value "SMAJ6.0CAHE3/5A")
      (footprint "VISH-DO-214AC-2_L")
      (fields (field (name "MANUFACTURER") "Vishay Semiconductor"))
      (libsource (lib "SMAJ6p0CAHE3") (part "CMP-0548-00108-2"))
    )
    (comp (ref "D3_1")
      (value "PESD2V0Y1BSFYL")
      (footprint "FP-SOD962-2-MFG")
      (description "TVS DIODE 2VWM 3VC DSN0603-2")
      (libsource (lib "Altium Content Vault") (part "3b819f4016a974b32db02c4901e5706"))
    )
    (comp (ref "D4_1")
      (value "ESDS311DYFR")
      (footprint "FP-DYF0002A-IPC_B")
      (libsource (lib "Altium Content Vault") (part "d0b9196d99f40cb8efe007e69fff614"))
    )
    (comp (ref "D5_1")
      (value "SMAJ6.0CAHE3/5A")
      (footprint "VISH-DO-214AC-2_L")
      (fields (field (name "MANUFACTURER") "Vishay Semiconductor"))
      (libsource (lib "SMAJ6p0CAHE3") (part "CMP-0548-00108-2"))
    )
    (comp (ref "D6_1")
      (value "PESD2V0Y1BSFYL")
      (footprint "FP-SOD962-2-MFG")
      (description "TVS DIODE 2VWM 3VC DSN0603-2")
      (libsource (lib "Altium Content Vault") (part "3b819f4016a974b32db02c4901e5706"))
    )
    (comp (ref "D7_1")
      (value "SMAJ6.0CAHE3/5A")
      (footprint "VISH-DO-214AC-2_L")
      (fields (field (name "MANUFACTURER") "Vishay Semiconductor"))
      (libsource (lib "SMAJ6p0CAHE3") (part "CMP-0548-00108-2"))
    )
    (comp (ref "J_ADC1_RST")
      (value "878980304")
      (footprint "CONN03_87898_M-5p84_MOL")
      (description "No Description Available")
      (libsource (lib "878980304") (part "878980304"))
    )
    (comp (ref "J_AVDD")
      (value "5019")
      (footprint "FP-5019-MFG")
      (libsource (lib "Altium Content Vault") (part "98815daf2f2c152b0c43f5ab9800df6"))
    )
    (comp (ref "J_CVDD")
      (value "5019")
      (footprint "FP-5019-MFG")
      (libsource (lib "Altium Content Vault") (part "98815daf2f2c152b0c43f5ab9800df6"))
    )
    (comp (ref "J_DVDD")
      (value "5019")
      (footprint "FP-5019-MFG")
      (libsource (lib "Altium Content Vault") (part "98815daf2f2c152b0c43f5ab9800df6"))
    )
    (comp (ref "J_GND5")
      (value "5019")
      (footprint "FP-5019-MFG")
      (libsource (lib "") (part "98815daf2f2c152b0c43f5ab9800df6_1"))
    )
    (comp (ref "J_GND6")
      (value "5019")
      (footprint "FP-5019-MFG")
      (libsource (lib "") (part "98815daf2f2c152b0c43f5ab9800df6_1"))
    )
    (comp (ref "LDO_AVDD1")
      (value "LT3073AVPBF")
      (footprint "05-08-7054_ADI")
      (description "No Description Available")
      (libsource (lib "LT3073AVPBF") (part "LT3073AVPBF"))
    )
    (comp (ref "LDO_AVDD2")
      (value "LT3074AVPBF")
      (footprint "LGA_CC-22-4_ADI")
      (description "No Description Available")
      (libsource (lib "LT3074AVPBF") (part "LT3074AVPBF"))
    )
    (comp (ref "LDO_CVDD1")
      (value "LT3073AVPBF")
      (footprint "05-08-7054_ADI")
      (description "No Description Available")
      (libsource (lib "LT3073AVPBF") (part "LT3073AVPBF"))
    )
    (comp (ref "LDO_CVDD2")
      (value "LT3074AVPBF")
      (footprint "LGA_CC-22-4_ADI")
      (description "No Description Available")
      (libsource (lib "LT3074AVPBF") (part "LT3074AVPBF"))
    )
    (comp (ref "LDO_DVDD1")
      (value "LT3073AVPBF")
      (footprint "05-08-7054_ADI")
      (description "No Description Available")
      (libsource (lib "LT3073AVPBF") (part "LT3073AVPBF"))
    )
    (comp (ref "LDO_DVDD2")
      (value "LT3074AVPBF")
      (footprint "LGA_CC-22-4_ADI")
      (description "No Description Available")
      (libsource (lib "LT3074AVPBF") (part "LT3074AVPBF"))
    )
    (comp (ref "R1_1")
      (value "51.1k")
      (footprint "FP-ERJ3EK-MFG")
      (fields (field (name "TOLERANCE") "1%"))
      (libsource (lib "res_0603_51p1k") (part "CMP-1012-00704-3"))
    )
    (comp (ref "R2_1")
      (value "2260")
      (footprint "RESC1005X40X25NL05T05")
      (fields (field (name "MANUFACTURER") "Panasonic") (field (name "PART NUMBER") "ERJ-2RKF2261X"))
      (libsource (lib "res_2260ohm_0402") (part "CMP-2002-00782-1"))
    )
    (comp (ref "R3_1")
      (value "2260")
      (footprint "RESC1005X40X25NL05T05")
      (fields (field (name "MANUFACTURER") "Panasonic") (field (name "PART NUMBER") "ERJ-2RKF2261X"))
      (libsource (lib "res_2260ohm_0402") (part "CMP-2002-00782-1"))
    )
    (comp (ref "R4_1")
      (value "2260")
      (footprint "RESC1005X40X25NL05T05")
      (fields (field (name "MANUFACTURER") "Panasonic") (field (name "PART NUMBER") "ERJ-2RKF2261X"))
      (libsource (lib "res_2260ohm_0402") (part "CMP-2002-00782-1"))
    )
    (comp (ref "R5_1")
      (value "294k")
      (footprint "RESC1005X40X25ML05T05")
      (description "RES SMD 294K OHM 1% 1/10W 0402")
      (fields (field (name "PART NUMBER") "ERJ-2RKF2943X") (field (name "MANUFACTURER") "Panasonic"))
      (libsource (lib "Altium Content Vault") (part "RES"))
    )
    (comp (ref "R6_1")
      (value "806")
      (footprint "RESC1005X40X25ML05T05")
      (fields (field (name "MANUFACTURER") "Panasonic") (field (name "PART NUMBER") "ERJ-2RKF8060X"))
      (libsource (lib "Altium Content Vault") (part "RES"))
    )
    (comp (ref "R7_1")
      (value "147k")
      (footprint "RESC1005X40X25NL05T05")
      (description "RES SMD 147K OHM 1% 1/10W 0402")
      (fields (field (name "PART NUMBER") "ERJ-2RKF1473X") (field (name "MANUFACTURER") "Panasonic"))
      (libsource (lib "Altium Content Vault") (part "RES"))
    )
    (comp (ref "R8_1")
      (value "47.5k")
      (footprint "FP-ERJ2RK-MFG")
      (description "RES SMD 47.5K OHM 1% 1/10W 0402")
      (fields (field (name "TOLERANCE") "1%"))
      (libsource (lib "Altium Content Vault") (part "1029c3af85768c4190bb7ad29bc67b5"))
    )
    (comp (ref "R9_1")
      (value "261k")
      (footprint "RESC1005X40X25LL05T05")
      (fields (field (name "MANUFACTURER") "Panasonic") (field (name "PART NUMBER") "ERJ-2RKF2613X"))
      (libsource (lib "Altium Content Vault") (part "RES"))
    )
    (comp (ref "R10_1")
      (value "2k")
      (footprint "RESC1608X55X30ML15T15")
      (fields (field (name "PART NUMBER") "ERJ-3EKF2001V") (field (name "MANUFACTURER") "Panasonic"))
      (libsource (lib "Altium Content Vault") (part "RES"))
    )
    (comp (ref "R11_1")
      (value "2k")
      (footprint "RESC1608X55X30ML15T15")
      (fields (field (name "PART NUMBER") "ERJ-3EKF2001V") (field (name "MANUFACTURER") "Panasonic"))
      (libsource (lib "Altium Content Vault") (part "RES"))
    )
    (comp (ref "R12_1")
      (value "8k")
      (footprint "FP-RT0603-0_55-MFG")
      (fields (field (name "TOLERANCE") "0.1%"))
      (libsource (lib "Altium Content Vault") (part "1029c3af85768c4190bb7ad29bc67b5"))
    )
    (comp (ref "R13_1")
      (value "1k")
      (footprint "RESC1608X55X30LL15T15")
      (fields (field (name "PART NUMBER") "ERJ-3EKF1001V") (field (name "MANUFACTURER") "Panasonic"))
      (libsource (lib "res_0603_1k") (part "CMP-2000-00180-1"))
    )
    (comp (ref "R14_1")
      (value "2k")
      (footprint "RESC1608X55X30ML15T15")
      (fields (field (name "PART NUMBER") "ERJ-3EKF2001V") (field (name "MANUFACTURER") "Panasonic"))
      (libsource (lib "Altium Content Vault") (part "RES"))
    )
    (comp (ref "R15_1")
      (value "2k")
      (footprint "RESC1608X55X30ML15T15")
      (fields (field (name "PART NUMBER") "ERJ-3EKF2001V") (field (name "MANUFACTURER") "Panasonic"))
      (libsource (lib "Altium Content Vault") (part "RES"))
    )
    (comp (ref "R16_1")
      (value "1k")
      (footprint "RESC1608X55X30LL15T15")
      (fields (field (name "PART NUMBER") "ERJ-3EKF1001V") (field (name "MANUFACTURER") "Panasonic"))
      (libsource (lib "res_0603_1k") (part "CMP-2000-00180-1"))
    )
    (comp (ref "R17_1")
      (value "51.1k")
      (footprint "FP-ERJ3EK-MFG")
      (fields (field (name "TOLERANCE") "1%"))
      (libsource (lib "res_0603_51p1k") (part "CMP-1012-00704-3"))
    )
    (comp (ref "R18_1")
      (value "294k")
      (footprint "RESC1005X40X25ML05T05")
      (description "RES SMD 294K OHM 1% 1/10W 0402")
      (fields (field (name "PART NUMBER") "ERJ-2RKF2943X") (field (name "MANUFACTURER") "Panasonic"))
      (libsource (lib "Altium Content Vault") (part "RES"))
    )
    (comp (ref "R19_1")
      (value "806")
      (footprint "RESC1005X40X25ML05T05")
      (fields (field (name "MANUFACTURER") "Panasonic") (field (name "PART NUMBER") "ERJ-2RKF8060X"))
      (libsource (lib "Altium Content Vault") (part "RES"))
    )
    (comp (ref "R20_1")
      (value "147k")
      (footprint "RESC1005X40X25NL05T05")
      (description "RES SMD 147K OHM 1% 1/10W 0402")
      (fields (field (name "PART NUMBER") "ERJ-2RKF1473X") (field (name "MANUFACTURER") "Panasonic"))
      (libsource (lib "Altium Content Vault") (part "RES"))
    )
    (comp (ref "R21_1")
      (value "100k")
      (footprint "FP-ERJ2RK-MFG")
      (description "RES SMD 100K OHM 1% 1/10W 0402")
      (fields (field (name "TOLERANCE") "1%"))
      (libsource (lib "Altium Content Vault") (part "1029c3af85768c4190bb7ad29bc67b5"))
    )
    (comp (ref "R22_1")
      (value "232k")
      (footprint "RESC1005X40X25LL05T05")
      (fields (field (name "MANUFACTURER") "Panasonic") (field (name "PART NUMBER") "ERJ-2RKF2323X"))
      (libsource (lib "Altium Content Vault") (part "RES"))
    )
    (comp (ref "R23_1")
      (value "8k")
      (footprint "FP-RT0603-0_55-MFG")
      (fields (field (name "TOLERANCE") "0.1%"))
      (libsource (lib "Altium Content Vault") (part "1029c3af85768c4190bb7ad29bc67b5"))
    )
    (comp (ref "R24_1")
      (value "1k")
      (footprint "RESC1608X55X30LL15T15")
      (fields (field (name "PART NUMBER") "ERJ-3EKF1001V") (field (name "MANUFACTURER") "Panasonic"))
      (libsource (lib "res_0603_1k") (part "CMP-2000-00180-1"))
    )
    (comp (ref "R25_1")
      (value "51.1k")
      (footprint "FP-ERJ3EK-MFG")
      (fields (field (name "TOLERANCE") "1%"))
      (libsource (lib "res_0603_51p1k") (part "CMP-1012-00704-3"))
    )
    (comp (ref "R26_1")
      (value "196k")
      (footprint "RESC1005X40X25NL05T05")
      (description "RES SMD 196K OHM 1% 1/10W 0402")
      (fields (field (name "MANUFACTURER") "Panasonic") (field (name "PART NUMBER") "ERJ-2RKF1963X"))
      (libsource (lib "Altium Content Vault") (part "RES"))
    )
    (comp (ref "R27_1")
      (value "147k")
      (footprint "RESC1005X40X25NL05T05")
      (description "RES SMD 147K OHM 1% 1/10W 0402")
      (fields (field (name "PART NUMBER") "ERJ-2RKF1473X") (field (name "MANUFACTURER") "Panasonic"))
      (libsource (lib "Altium Content Vault") (part "RES"))
    )
    (comp (ref "R28_1")
      (value "806")
      (footprint "RESC1005X40X25ML05T05")
      (fields (field (name "MANUFACTURER") "Panasonic") (field (name "PART NUMBER") "ERJ-2RKF8060X"))
      (libsource (lib "Altium Content Vault") (part "RES"))
    )
    (comp (ref "R29_1")
      (value "124k")
      (footprint "FP-ERJ2RK-MFG")
      (fields (field (name "TOLERANCE") "1%"))
      (libsource (lib "Altium Content Vault") (part "1029c3af85768c4190bb7ad29bc67b5"))
    )
    (comp (ref "R30_1")
      (value "84.5k")
      (footprint "RESC1005X40X25ML05T05")
      (fields (field (name "MANUFACTURER") "Panasonic") (field (name "PART NUMBER") "ERJ-2RKF8452X"))
      (libsource (lib "Altium Content Vault") (part "RES"))
    )
    (comp (ref "R31_1")
      (value "8k")
      (footprint "FP-RT0603-0_55-MFG")
      (fields (field (name "TOLERANCE") "0.1%"))
      (libsource (lib "Altium Content Vault") (part "1029c3af85768c4190bb7ad29bc67b5"))
    )
    (comp (ref "R32_1")
      (value "1k")
      (footprint "RESC1608X55X30LL15T15")
      (fields (field (name "PART NUMBER") "ERJ-3EKF1001V") (field (name "MANUFACTURER") "Panasonic"))
      (libsource (lib "res_0603_1k") (part "CMP-2000-00180-1"))
    )
    (comp (ref "R33_1")
      (value "DNP")
      (footprint "FP-CPF0603-IPC_C")
      (description "RES SMD 1.4KΩ 0.1% 1/16W 0603")
      (fields (field (name "TOLERANCE") "0.1%") (field (name "MANUFACTURER PART NUMBER") "CPF0603B1K4E1"))
      (libsource (lib "res_0603_1p4k") (part "CMP-03211-004406-1"))
    )
    (comp (ref "R34_1")
      (value "1.4k")
      (footprint "FP-CPF0603-IPC_C")
      (description "RES SMD 1.4KΩ 0.1% 1/16W 0603")
      (fields (field (name "TOLERANCE") "0.1%") (field (name "MANUFACTURER PART NUMBER") "CPF0603B1K4E1"))
      (libsource (lib "res_0603_1p4k") (part "CMP-03211-004406-1"))
    )
    (comp (ref "R35_1")
      (value "DNP")
      (footprint "FP-CPF0603-IPC_C")
      (description "RES SMD 1.4KΩ 0.1% 1/16W 0603")
      (fields (field (name "TOLERANCE") "0.1%") (field (name "MANUFACTURER PART NUMBER") "CPF0603B1K4E1"))
      (libsource (lib "res_0603_1p4k") (part "CMP-03211-004406-1"))
    )
    (comp (ref "R36_1")
      (value "1.4k")
      (footprint "FP-CPF0603-IPC_C")
      (description "RES SMD 1.4KΩ 0.1% 1/16W 0603")
      (fields (field (name "TOLERANCE") "0.1%") (field (name "MANUFACTURER PART NUMBER") "CPF0603B1K4E1"))
      (libsource (lib "res_0603_1p4k") (part "CMP-03211-004406-1"))
    )
    (comp (ref "R37_1")
      (value "DNP")
      (footprint "FP-CPF0603-IPC_C")
      (description "RES SMD 1.4KΩ 0.1% 1/16W 0603")
      (fields (field (name "TOLERANCE") "0.1%") (field (name "MANUFACTURER PART NUMBER") "CPF0603B1K4E1"))
      (libsource (lib "res_0603_1p4k") (part "CMP-03211-004406-1"))
    )
    (comp (ref "R38_1")
      (value "1.4k")
      (footprint "FP-CPF0603-IPC_C")
      (description "RES SMD 1.4KΩ 0.1% 1/16W 0603")
      (fields (field (name "TOLERANCE") "0.1%") (field (name "MANUFACTURER PART NUMBER") "CPF0603B1K4E1"))
      (libsource (lib "res_0603_1p4k") (part "CMP-03211-004406-1"))
    )
    (comp (ref "R39_1")
      (value "0")
      (footprint "FP-CRG0603-IPC_A")
      (description "RES SMD 0 OHM JUMPER 1/10W 0603")
      (fields (field (name "TOLERANCE") "0%"))
      (libsource (lib "Altium Content Vault") (part "1029c3af85768c4190bb7ad29bc67b5"))
    )
    (comp (ref "U_AVDD_IMON")
      (value "OPA210IDBVR")
      (footprint "FP-DBV0005A-MFG")
      (description "3.3-V, LOW-DRIFT, LOW-POWER, SMA")
      (libsource (lib "Altium Content Vault") (part "1dcd28e651784f0a5a8ed6f8452eeff"))
    )
    (comp (ref "U_AVDD_POT")
      (value "AD5245BRJZ5-RL7")
      (footprint "FP-RJ-8-IPC_A")
      (description "IC DGTL POT 5KOHM 256TAP SOT23-8")
      (fields
        (field (name "TOLERANCE") "30%")
        (field (name "OCTOPART") "https://octopart.com/ad5245brjz5-rl7-analog+devices-446720")
      )
      (libsource (lib "Altium Content Vault") (part "5227bb8a486013366a734e1709cf8d9"))
    )
    (comp (ref "U_CVDD_IMON")
      (value "OPA210IDBVR")
      (footprint "FP-DBV0005A-MFG")
      (description "3.3-V, LOW-DRIFT, LOW-POWER, SMA")
      (libsource (lib "Altium Content Vault") (part "1dcd28e651784f0a5a8ed6f8452eeff"))
    )
    (comp (ref "U_CVDD_POT")
      (value "AD5245BRJZ5-RL7")
      (footprint "FP-RJ-8-IPC_A")
      (description "IC DGTL POT 5KOHM 256TAP SOT23-8")
      (fields
        (field (name "TOLERANCE") "30%")
        (field (name "OCTOPART") "https://octopart.com/ad5245brjz5-rl7-analog+devices-446720")
      )
      (libsource (lib "Altium Content Vault") (part "5227bb8a486013366a734e1709cf8d9"))
    )
    (comp (ref "U_DVDD_IMON")
      (value "OPA210IDBVR")
      (footprint "FP-DBV0005A-MFG")
      (description "3.3-V, LOW-DRIFT, LOW-POWER, SMA")
      (libsource (lib "Altium Content Vault") (part "1dcd28e651784f0a5a8ed6f8452eeff"))
    )
    (comp (ref "U_DVDD_POT")
      (value "MCP4551T-502E/MS")
      (footprint "MSOP-MS8_L")
      (description "8-Bit Single I2C Digital POT with Volatile Memory, 8-pin MSOP, Extended Temperature, Tape and Reel")
      (libsource (lib "MCP4551T_502E") (part "CMP-0188-00126-2"))
    )
  )
  (nets
    (net (code "1") (name "/AVDD_ASEL") (class "Default")
      (node (ref "LDO_AVDD2") (pin "15") (pinfunction "ASEL_15") (pintype "passive"))
      (node (ref "R8_1") (pin "1") (pinfunction "1_1") (pintype "passive"))
      (node (ref "R9_1") (pin "2") (pinfunction "2_2") (pintype "passive"))
    )
    (net (code "2") (name "/AVDD_BIASAF") (class "Default")
      (node (ref "C9_1") (pin "2") (pinfunction "2_2") (pintype "passive"))
      (node (ref "LDO_AVDD2") (pin "16") (pinfunction "BIASAF_16") (pintype "passive"))
      (node (ref "R8_1") (pin "2") (pinfunction "2_2") (pintype "passive"))
    )
    (net (code "3") (name "/AVDD_EN") (class "Default")
      (node (ref "LDO_AVDD2") (pin "22") (pinfunction "EN_22") (pintype "passive"))
    )
    (net (code "4") (name "/AVDD_P1V6") (class "Default")
      (node (ref "C6_1") (pin "2") (pinfunction "GND_2") (pintype "passive"))
      (node (ref "C7_1") (pin "2") (pinfunction "GND_2") (pintype "passive"))
      (node (ref "LDO_AVDD1") (pin "10") (pinfunction "SENSE_10") (pintype "input"))
      (node (ref "LDO_AVDD1") (pin "24") (pinfunction "OUT_24") (pintype "output"))
      (node (ref "LDO_AVDD1") (pin "7") (pinfunction "OUT_7") (pintype "output"))
      (node (ref "LDO_AVDD1") (pin "8") (pinfunction "OUT_8") (pintype "output"))
      (node (ref "LDO_AVDD1") (pin "9") (pinfunction "OUT_9") (pintype "output"))
      (node (ref "LDO_AVDD2") (pin "20") (pinfunction "IN_20") (pintype "power_in"))
      (node (ref "LDO_AVDD2") (pin "21") (pinfunction "IN_21") (pintype "power_in"))
      (node (ref "LDO_AVDD2") (pin "23") (pinfunction "IN_23") (pintype "power_in"))
    )
    (net (code "5") (name "/AVDD_P2V1") (class "Default")
      (node (ref "C18_1") (pin "2") (pinfunction "A_2") (pintype "passive"))
      (node (ref "C23_1") (pin "2") (pinfunction "GND_2") (pintype "passive"))
      (node (ref "C24_1") (pin "2") (pinfunction "GND_2") (pintype "passive"))
      (node (ref "D2_1") (pin "1") (pinfunction "A1_1") (pintype "passive"))
      (node (ref "LDO_AVDD1") (pin "20") (pinfunction "IN_20") (pintype "input"))
      (node (ref "LDO_AVDD1") (pin "21") (pinfunction "IN_21") (pintype "input"))
      (node (ref "LDO_AVDD1") (pin "22") (pinfunction "IN_22") (pintype "input"))
      (node (ref "LDO_AVDD1") (pin "23") (pinfunction "IN_23") (pintype "input"))
    )
    (net (code "6") (name "/A_VIOC") (class "Default")
      (node (ref "LDO_AVDD2") (pin "2") (pinfunction "VIOC_2") (pintype "passive"))
    )
    (net (code "7") (name "/CVDD_ASEL") (class "Default")
      (node (ref "LDO_CVDD2") (pin "15") (pinfunction "ASEL_15") (pintype "passive"))
      (node (ref "R21_1") (pin "1") (pinfunction "1_1") (pintype "passive"))
      (node (ref "R22_1") (pin "2") (pinfunction "2_2") (pintype "passive"))
    )
    (net (code "8") (name "/CVDD_BIASAF") (class "Default")
      (node (ref "C39_1") (pin "2") (pinfunction "2_2") (pintype "passive"))
      (node (ref "LDO_CVDD2") (pin "16") (pinfunction "BIASAF_16") (pintype "passive"))
      (node (ref "R21_1") (pin "2") (pinfunction "2_2") (pintype "passive"))
    )
    (net (code "9") (name "/CVDD_EN") (class "Default")
      (node (ref "LDO_CVDD2") (pin "22") (pinfunction "EN_22") (pintype "passive"))
    )
    (net (code "10") (name "/CVDD_P1V6") (class "Default")
      (node (ref "C36_1") (pin "2") (pinfunction "GND_2") (pintype "passive"))
      (node (ref "C37_1") (pin "2") (pinfunction "GND_2") (pintype "passive"))
      (node (ref "LDO_CVDD1") (pin "10") (pinfunction "SENSE_10") (pintype "input"))
      (node (ref "LDO_CVDD1") (pin "24") (pinfunction "OUT_24") (pintype "output"))
      (node (ref "LDO_CVDD1") (pin "7") (pinfunction "OUT_7") (pintype "output"))
      (node (ref "LDO_CVDD1") (pin "8") (pinfunction "OUT_8") (pintype "output"))
      (node (ref "LDO_CVDD1") (pin "9") (pinfunction "OUT_9") (pintype "output"))
      (node (ref "LDO_CVDD2") (pin "20") (pinfunction "IN_20") (pintype "power_in"))
      (node (ref "LDO_CVDD2") (pin "21") (pinfunction "IN_21") (pintype "power_in"))
      (node (ref "LDO_CVDD2") (pin "23") (pinfunction "IN_23") (pintype "power_in"))
    )
    (net (code "11") (name "/CVDD_P2V1") (class "Default")
      (node (ref "C43_1") (pin "2") (pinfunction "A_2") (pintype "passive"))
      (node (ref "C46_1") (pin "2") (pinfunction "GND_2") (pintype "passive"))
      (node (ref "C47_1") (pin "2") (pinfunction "GND_2") (pintype "passive"))
      (node (ref "D5_1") (pin "1") (pinfunction "A1_1") (pintype "passive"))
      (node (ref "LDO_CVDD1") (pin "20") (pinfunction "IN_20") (pintype "input"))
      (node (ref "LDO_CVDD1") (pin "21") (pinfunction "IN_21") (pintype "input"))
      (node (ref "LDO_CVDD1") (pin "22") (pinfunction "IN_22") (pintype "input"))
      (node (ref "LDO_CVDD1") (pin "23") (pinfunction "IN_23") (pintype "input"))
    )
    (net (code "12") (name "/CVDD_VIOC") (class "Default")
      (node (ref "LDO_CVDD2") (pin "2") (pinfunction "VIOC_2") (pintype "passive"))
    )
    (net (code "13") (name "/DVDD_ASEL") (class "Default")
      (node (ref "LDO_DVDD2") (pin "15") (pinfunction "ASEL_15") (pintype "passive"))
      (node (ref "R29_1") (pin "1") (pinfunction "1_1") (pintype "passive"))
      (node (ref "R30_1") (pin "2") (pinfunction "2_2") (pintype "passive"))
    )
    (net (code "14") (name "/DVDD_BIASAF") (class "Default")
      (node (ref "C64_1") (pin "2") (pinfunction "2_2") (pintype "passive"))
      (node (ref "LDO_DVDD2") (pin "16") (pinfunction "BIASAF_16") (pintype "passive"))
      (node (ref "R29_1") (pin "2") (pinfunction "2_2") (pintype "passive"))
    )
    (net (code "15") (name "/DVDD_EN") (class "Default")
      (node (ref "LDO_DVDD2") (pin "22") (pinfunction "EN_22") (pintype "passive"))
    )
    (net (code "16") (name "/DVDD_P1V6") (class "Default")
      (node (ref "C61_1") (pin "2") (pinfunction "GND_2") (pintype "passive"))
      (node (ref "C62_1") (pin "2") (pinfunction "GND_2") (pintype "passive"))
      (node (ref "LDO_DVDD1") (pin "10") (pinfunction "SENSE_10") (pintype "input"))
      (node (ref "LDO_DVDD1") (pin "24") (pinfunction "OUT_24") (pintype "output"))
      (node (ref "LDO_DVDD1") (pin "7") (pinfunction "OUT_7") (pintype "output"))
      (node (ref "LDO_DVDD1") (pin "8") (pinfunction "OUT_8") (pintype "output"))
      (node (ref "LDO_DVDD1") (pin "9") (pinfunction "OUT_9") (pintype "output"))
      (node (ref "LDO_DVDD2") (pin "20") (pinfunction "IN_20") (pintype "power_in"))
      (node (ref "LDO_DVDD2") (pin "21") (pinfunction "IN_21") (pintype "power_in"))
      (node (ref "LDO_DVDD2") (pin "23") (pinfunction "IN_23") (pintype "power_in"))
    )
    (net (code "17") (name "/DVDD_P2V1") (class "Default")
      (node (ref "C79_1") (pin "2") (pinfunction "A_2") (pintype "passive"))
      (node (ref "C82_1") (pin "2") (pinfunction "GND_2") (pintype "passive"))
      (node (ref "C83_1") (pin "2") (pinfunction "GND_2") (pintype "passive"))
      (node (ref "D7_1") (pin "1") (pinfunction "A1_1") (pintype "passive"))
      (node (ref "LDO_DVDD1") (pin "20") (pinfunction "IN_20") (pintype "input"))
      (node (ref "LDO_DVDD1") (pin "21") (pinfunction "IN_21") (pintype "input"))
      (node (ref "LDO_DVDD1") (pin "22") (pinfunction "IN_22") (pintype "input"))
      (node (ref "LDO_DVDD1") (pin "23") (pinfunction "IN_23") (pintype "input"))
    )
    (net (code "18") (name "/D_VIOC") (class "Default")
      (node (ref "LDO_DVDD2") (pin "2") (pinfunction "VIOC_2") (pintype "passive+no_connect"))
    )
    (net (code "19") (name "/IMON_AVDD") (class "Default")
      (node (ref "LDO_AVDD2") (pin "14") (pinfunction "IMON_14") (pintype "power_in"))
      (node (ref "U_AVDD_IMON") (pin "3") (pinfunction "+IN_3") (pintype "tri_state"))
    )
    (net (code "20") (name "/IMON_AVDD_BUF") (class "Default")
      (node (ref "ADC_1") (pin "11") (pinfunction "AIN0_11") (pintype "passive"))
      (node (ref "C27_1") (pin "1") (pinfunction "1_1") (pintype "passive"))
      (node (ref "R13_1") (pin "1") (pinfunction "1_1") (pintype "passive"))
    )
    (net (code "21") (name "/IMON_CVDD") (class "Default")
      (node (ref "LDO_CVDD2") (pin "14") (pinfunction "IMON_14") (pintype "power_in"))
      (node (ref "U_CVDD_IMON") (pin "3") (pinfunction "+IN_3") (pintype "tri_state"))
    )
    (net (code "22") (name "/IMON_CVDD_BUF") (class "Default")
      (node (ref "ADC_1") (pin "7") (pinfunction "AIN2_7") (pintype "passive"))
      (node (ref "C55_1") (pin "1") (pinfunction "1_1") (pintype "passive"))
      (node (ref "R24_1") (pin "1") (pinfunction "1_1") (pintype "passive"))
    )
    (net (code "23") (name "/IMON_DVDD") (class "Default")
      (node (ref "LDO_DVDD2") (pin "14") (pinfunction "IMON_14") (pintype "power_in"))
      (node (ref "U_DVDD_IMON") (pin "3") (pinfunction "+IN_3") (pintype "tri_state"))
    )
    (net (code "24") (name "/IMON_DVDD_BUF") (class "Default")
      (node (ref "ADC_1") (pin "6") (pinfunction "AIN3_6") (pintype "passive"))
      (node (ref "C85_1") (pin "1") (pinfunction "1_1") (pintype "passive"))
      (node (ref "R32_1") (pin "1") (pinfunction "1_1") (pintype "passive"))
    )
    (net (code "25") (name "/PMB_ALT") (class "Default")
      (node (ref "LDO_AVDD2") (pin "3") (pinfunction "*ALERT_3") (pintype "output"))
      (node (ref "LDO_CVDD2") (pin "3") (pinfunction "*ALERT_3") (pintype "output"))
      (node (ref "LDO_DVDD2") (pin "3") (pinfunction "*ALERT_3") (pintype "output"))
      (node (ref "R4_1") (pin "1") (pinfunction "1_1") (pintype "passive"))
    )
    (net (code "26") (name "/PMB_SCL") (class "Default")
      (node (ref "LDO_AVDD2") (pin "4") (pinfunction "SCL_4") (pintype "output"))
      (node (ref "LDO_CVDD2") (pin "4") (pinfunction "SCL_4") (pintype "output"))
      (node (ref "LDO_DVDD2") (pin "4") (pinfunction "SCL_4") (pintype "output"))
      (node (ref "R3_1") (pin "1") (pinfunction "1_1") (pintype "passive"))
    )
    (net (code "27") (name "/PMB_SDA") (class "Default")
      (node (ref "LDO_AVDD2") (pin "5") (pinfunction "SDA_5") (pintype "output"))
      (node (ref "LDO_CVDD2") (pin "5") (pinfunction "SDA_5") (pintype "output"))
      (node (ref "LDO_DVDD2") (pin "5") (pinfunction "SDA_5") (pintype "output"))
      (node (ref "R2_1") (pin "1") (pinfunction "1_1") (pintype "passive"))
    )
    (net (code "28") (name "/SCL_P2V5") (class "Default")
      (node (ref "ADC_1") (pin "16") (pinfunction "SCL_16") (pintype "input"))
      (node (ref "R15_1") (pin "1") (pinfunction "1_1") (pintype "passive"))
    )
    (net (code "29") (name "/SCL_P3V3") (class "Default")
      (node (ref "R10_1") (pin "1") (pinfunction "1_1") (pintype "passive"))
      (node (ref "U_AVDD_POT") (pin "4") (pinfunction "SCL_4") (pintype "input"))
      (node (ref "U_CVDD_POT") (pin "4") (pinfunction "SCL_4") (pintype "input"))
      (node (ref "U_DVDD_POT") (pin "2") (pinfunction "SCL_2") (pintype "input"))
    )
    (net (code "30") (name "/SDA_P2V5") (class "Default")
      (node (ref "ADC_1") (pin "15") (pinfunction "SDA_15") (pintype "bidirectional"))
      (node (ref "R14_1") (pin "1") (pinfunction "1_1") (pintype "passive"))
    )
    (net (code "31") (name "/SDA_P3V3") (class "Default")
      (node (ref "R11_1") (pin "1") (pinfunction "1_1") (pintype "passive"))
      (node (ref "U_AVDD_POT") (pin "5") (pinfunction "SDA_5") (pintype "bidirectional"))
      (node (ref "U_CVDD_POT") (pin "5") (pinfunction "SDA_5") (pintype "bidirectional"))
      (node (ref "U_DVDD_POT") (pin "3") (pinfunction "SDA_3") (pintype "bidirectional"))
    )
    (net (code "33") (name "AVDD_P1V1") (class "Default")
      (node (ref "C12_1") (pin "2") (pinfunction "GND_2") (pintype "passive"))
      (node (ref "C13_1") (pin "2") (pinfunction "GND_2") (pintype "passive"))
      (node (ref "C14_1") (pin "2") (pinfunction "GND_2") (pintype "passive"))
      (node (ref "C15_1") (pin "2") (pinfunction "GND_2") (pintype "passive"))
      (node (ref "C16_1") (pin "2") (pinfunction "GND_2") (pintype "passive"))
      (node (ref "C17_1") (pin "2") (pinfunction "GND_2") (pintype "passive"))
      (node (ref "C1_1") (pin "2") (pinfunction "GND_2") (pintype "passive"))
      (node (ref "C21_1") (pin "2") (pinfunction "GND_2") (pintype "passive"))
      (node (ref "C22_1") (pin "2") (pinfunction "GND_2") (pintype "passive"))
      (node (ref "C2_1") (pin "2") (pinfunction "GND_2") (pintype "passive"))
      (node (ref "C3_1") (pin "2") (pinfunction "GND_2") (pintype "passive"))
      (node (ref "C4_1") (pin "2") (pinfunction "GND_2") (pintype "passive"))
      (node (ref "D1_1") (pin "1") (pinfunction "K1_1") (pintype "passive"))
      (node (ref "J_AVDD") (pin "1") (pinfunction "1_1") (pintype "passive"))
      (node (ref "LDO_AVDD2") (pin "10") (pinfunction "SENSE_10") (pintype "input"))
      (node (ref "LDO_AVDD2") (pin "24") (pinfunction "OUT_24") (pintype "power_in"))
      (node (ref "LDO_AVDD2") (pin "8") (pinfunction "OUT_8") (pintype "power_in"))
      (node (ref "LDO_AVDD2") (pin "9") (pinfunction "OUT_9") (pintype "power_in"))
      (node (ref "R5_1") (pin "2") (pinfunction "2_2") (pintype "passive"))
    )
    (net (code "34") (name "CVDD_P1V1") (class "Default")
      (node (ref "C32_1") (pin "2") (pinfunction "GND_2") (pintype "passive"))
      (node (ref "C33_1") (pin "2") (pinfunction "GND_2") (pintype "passive"))
      (node (ref "C34_1") (pin "2") (pinfunction "GND_2") (pintype "passive"))
      (node (ref "C35_1") (pin "2") (pinfunction "GND_2") (pintype "passive"))
      (node (ref "C48_1") (pin "2") (pinfunction "GND_2") (pintype "passive"))
      (node (ref "C49_1") (pin "2") (pinfunction "GND_2") (pintype "passive"))
      (node (ref "C50_1") (pin "2") (pinfunction "GND_2") (pintype "passive"))
      (node (ref "C51_1") (pin "2") (pinfunction "GND_2") (pintype "passive"))
      (node (ref "C52_1") (pin "2") (pinfunction "GND_2") (pintype "passive"))
      (node (ref "D3_1") (pin "1") (pinfunction "K1_1") (pintype "passive"))
      (node (ref "J_CVDD") (pin "1") (pinfunction "1_1") (pintype "passive"))
      (node (ref "LDO_CVDD2") (pin "10") (pinfunction "SENSE_10") (pintype "input"))
      (node (ref "LDO_CVDD2") (pin "24") (pinfunction "OUT_24") (pintype "power_in"))
      (node (ref "LDO_CVDD2") (pin "8") (pinfunction "OUT_8") (pintype "power_in"))
      (node (ref "LDO_CVDD2") (pin "9") (pinfunction "OUT_9") (pintype "power_in"))
      (node (ref "R18_1") (pin "2") (pinfunction "2_2") (pintype "passive"))
    )
    (net (code "35") (name "DVDD_P0V85") (class "Default")
      (node (ref "C100_1") (pin "2") (pinfunction "GND_2") (pintype "passive"))
      (node (ref "C101_1") (pin "2") (pinfunction "GND_2") (pintype "passive"))
      (node (ref "C102_1") (pin "2") (pinfunction "GND_2") (pintype "passive"))
      (node (ref "C103_1") (pin "2") (pinfunction "GND_2") (pintype "passive"))
      (node (ref "C104_1") (pin "2") (pinfunction "GND_2") (pintype "passive"))
      (node (ref "C105_1") (pin "2") (pinfunction "GND_2") (pintype "passive"))
      (node (ref "C106_1") (pin "2") (pinfunction "GND_2") (pintype "passive"))
      (node (ref "C57_1") (pin "2") (pinfunction "GND_2") (pintype "passive"))
      (node (ref "C58_1") (pin "2") (pinfunction "GND_2") (pintype "passive"))
      (node (ref "C59_1") (pin "2") (pinfunction "GND_2") (pintype "passive"))
      (node (ref "C60_1") (pin "2") (pinfunction "GND_2") (pintype "passive"))
      (node (ref "C67_1") (pin "2") (pinfunction "GND_2") (pintype "passive"))
      (node (ref "C68_1") (pin "2") (pinfunction "GND_2") (pintype "passive"))
      (node (ref "C69_1") (pin "2") (pinfunction "GND_2") (pintype "passive"))
      (node (ref "C70_1") (pin "2") (pinfunction "GND_2") (pintype "passive"))
      (node (ref "C71_1") (pin "2") (pinfunction "GND_2") (pintype "passive"))
      (node (ref "C72_1") (pin "2") (pinfunction "GND_2") (pintype "passive"))
      (node (ref "C73_1") (pin "2") (pinfunction "GND_2") (pintype "passive"))
      (node (ref "C74_1") (pin "2") (pinfunction "GND_2") (pintype "passive"))
      (node (ref "C75_1") (pin "2") (pinfunction "GND_2") (pintype "passive"))
      (node (ref "C76_1") (pin "2") (pinfunction "GND_2") (pintype "passive"))
      (node (ref "C77_1") (pin "2") (pinfunction "GND_2") (pintype "passive"))
      (node (ref "C78_1") (pin "2") (pinfunction "GND_2") (pintype "passive"))
      (node (ref "C86_1") (pin "2") (pinfunction "GND_2") (pintype "passive"))
      (node (ref "C87_1") (pin "2") (pinfunction "GND_2") (pintype "passive"))
      (node (ref "C88_1") (pin "2") (pinfunction "GND_2") (pintype "passive"))
      (node (ref "C89_1") (pin "2") (pinfunction "GND_2") (pintype "passive"))
      (node (ref "C90_1") (pin "2") (pinfunction "GND_2") (pintype "passive"))
      (node (ref "C91_1") (pin "2") (pinfunction "GND_2") (pintype "passive"))
      (node (ref "C92_1") (pin "2") (pinfunction "GND_2") (pintype "passive"))
      (node (ref "C93_1") (pin "2") (pinfunction "GND_2") (pintype "passive"))
      (node (ref "C95_1") (pin "2") (pinfunction "GND_2") (pintype "passive"))
      (node (ref "C96_1") (pin "2") (pinfunction "GND_2") (pintype "passive"))
      (node (ref "C97_1") (pin "2") (pinfunction "GND_2") (pintype "passive"))
      (node (ref "C98_1") (pin "2") (pinfunction "GND_2") (pintype "passive"))
      (node (ref "C99_1") (pin "2") (pinfunction "GND_2") (pintype "passive"))
      (node (ref "D6_1") (pin "1") (pinfunction "K1_1") (pintype "passive"))
      (node (ref "J_DVDD") (pin "1") (pinfunction "1_1") (pintype "passive"))
      (node (ref "LDO_DVDD2") (pin "10") (pinfunction "SENSE_10") (pintype "input"))
      (node (ref "LDO_DVDD2") (pin "24") (pinfunction "OUT_24") (pintype "power_in"))
      (node (ref "LDO_DVDD2") (pin "8") (pinfunction "OUT_8") (pintype "power_in"))
      (node (ref "LDO_DVDD2") (pin "9") (pinfunction "OUT_9") (pintype "power_in"))
      (node (ref "R26_1") (pin "2") (pinfunction "2_2") (pintype "passive"))
    )
    (net (code "36") (name "GND") (class "Default")
      (node (ref "ADC_1") (pin "10") (pinfunction "AIN1_10") (pintype "passive"))
      (node (ref "ADC_1") (pin "4") (pinfunction "DGND_4") (pintype "power_in"))
      (node (ref "ADC_1") (pin "8") (pinfunction "REFN_8") (pintype "passive"))
      (node (ref "C100_1") (pin "1") (pinfunction "Input_1") (pintype "passive"))
      (node (ref "C100_1") (pin "3") (pinfunction "Output_3") (pintype "passive"))
      (node (ref "C101_1") (pin "1") (pinfunction "Input_1") (pintype "passive"))
      (node (ref "C101_1") (pin "3") (pinfunction "Output_3") (pintype "passive"))
      (node (ref "C102_1") (pin "1") (pinfunction "Input_1") (pintype "passive"))
      (node (ref "C102_1") (pin "3") (pinfunction "Output_3") (pintype "passive"))
      (node (ref "C103_1") (pin "1") (pinfunction "Input_1") (pintype "passive"))
      (node (ref "C103_1") (pin "3") (pinfunction "Output_3") (pintype "passive"))
      (node (ref "C104_1") (pin "1") (pinfunction "Input_1") (pintype "passive"))
      (node (ref "C104_1") (pin "3") (pinfunction "Output_3") (pintype "passive"))
      (node (ref "C105_1") (pin "1") (pinfunction "Input_1") (pintype "passive"))
      (node (ref "C105_1") (pin "3") (pinfunction "Output_3") (pintype "passive"))
      (node (ref "C106_1") (pin "1") (pinfunction "Input_1") (pintype "passive"))
      (node (ref "C106_1") (pin "3") (pinfunction "Output_3") (pintype "passive"))
      (node (ref "C10_1") (pin "1") (pinfunction "1_1") (pintype "passive"))
      (node (ref "C11_1") (pin "1") (pinfunction "1_1") (pintype "passive"))
      (node (ref "C12_1") (pin "1") (pinfunction "Input_1") (pintype "passive"))
      (node (ref "C12_1") (pin "3") (pinfunction "Output_3") (pintype "passive"))
      (node (ref "C13_1") (pin "1") (pinfunction "Input_1") (pintype "passive"))
      (node (ref "C13_1") (pin "3") (pinfunction "Output_3") (pintype "passive"))
      (node (ref "C14_1") (pin "1") (pinfunction "Input_1") (pintype "passive"))
      (node (ref "C14_1") (pin "3") (pinfunction "Output_3") (pintype "passive"))
      (node (ref "C15_1") (pin "1") (pinfunction "Input_1") (pintype "passive"))
      (node (ref "C15_1") (pin "3") (pinfunction "Output_3") (pintype "passive"))
      (node (ref "C16_1") (pin "1") (pinfunction "Input_1") (pintype "passive"))
      (node (ref "C16_1") (pin "3") (pinfunction "Output_3") (pintype "passive"))
      (node (ref "C17_1") (pin "1") (pinfunction "Input_1") (pintype "passive"))
      (node (ref "C17_1") (pin "3") (pinfunction "Output_3") (pintype "passive"))
      (node (ref "C18_1") (pin "1") (pinfunction "C_1") (pintype "passive"))
      (node (ref "C19_1") (pin "1") (pinfunction "1_1") (pintype "passive"))
      (node (ref "C1_1") (pin "1") (pinfunction "Input_1") (pintype "passive"))
      (node (ref "C1_1") (pin "3") (pinfunction "Output_3") (pintype "passive"))
      (node (ref "C20_1") (pin "1") (pinfunction "1_1") (pintype "passive"))
      (node (ref "C21_1") (pin "1") (pinfunction "Input_1") (pintype "passive"))
      (node (ref "C21_1") (pin "3") (pinfunction "Output_3") (pintype "passive"))
      (node (ref "C22_1") (pin "1") (pinfunction "Input_1") (pintype "passive"))
      (node (ref "C22_1") (pin "3") (pinfunction "Output_3") (pintype "passive"))
      (node (ref "C23_1") (pin "1") (pinfunction "Input_1") (pintype "passive"))
      (node (ref "C23_1") (pin "3") (pinfunction "Output_3") (pintype "passive"))
      (node (ref "C24_1") (pin "1") (pinfunction "Input_1") (pintype "passive"))
      (node (ref "C24_1") (pin "3") (pinfunction "Output_3") (pintype "passive"))
      (node (ref "C25_1") (pin "1") (pinfunction "Input_1") (pintype "passive"))
      (node (ref "C25_1") (pin "3") (pinfunction "Output_3") (pintype "passive"))
      (node (ref "C26_1") (pin "1") (pinfunction "Input_1") (pintype "passive"))
      (node (ref "C26_1") (pin "3") (pinfunction "Output_3") (pintype "passive"))
      (node (ref "C27_1") (pin "2") (pinfunction "2_2") (pintype "passive"))
      (node (ref "C28_1") (pin "1") (pinfunction "Input_1") (pintype "passive"))
      (node (ref "C28_1") (pin "3") (pinfunction "Output_3") (pintype "passive"))
      (node (ref "C29_1") (pin "2") (pinfunction "2_2") (pintype "passive"))
      (node (ref "C2_1") (pin "1") (pinfunction "Input_1") (pintype "passive"))
      (node (ref "C2_1") (pin "3") (pinfunction "Output_3") (pintype "passive"))
      (node (ref "C30_1") (pin "2") (pinfunction "2_2") (pintype "passive"))
      (node (ref "C31_1") (pin "2") (pinfunction "2_2") (pintype "passive"))
      (node (ref "C32_1") (pin "1") (pinfunction "Input_1") (pintype "passive"))
      (node (ref "C32_1") (pin "3") (pinfunction "Output_3") (pintype "passive"))
      (node (ref "C33_1") (pin "1") (pinfunction "Input_1") (pintype "passive"))
      (node (ref "C33_1") (pin "3") (pinfunction "Output_3") (pintype "passive"))
      (node (ref "C34_1") (pin "1") (pinfunction "Input_1") (pintype "passive"))
      (node (ref "C34_1") (pin "3") (pinfunction "Output_3") (pintype "passive"))
      (node (ref "C35_1") (pin "1") (pinfunction "Input_1") (pintype "passive"))
      (node (ref "C35_1") (pin "3") (pinfunction "Output_3") (pintype "passive"))
      (node (ref "C36_1") (pin "1") (pinfunction "Input_1") (pintype "passive"))
      (node (ref "C36_1") (pin "3") (pinfunction "Output_3") (pintype "passive"))
      (node (ref "C37_1") (pin "1") (pinfunction "Input_1") (pintype "passive"))
      (node (ref "C37_1") (pin "3") (pinfunction "Output_3") (pintype "passive"))
      (node (ref "C38_1") (pin "2") (pinfunction "2_2") (pintype "passive"))
      (node (ref "C39_1") (pin "1") (pinfunction "1_1") (pintype "passive"))
      (node (ref "C3_1") (pin "1") (pinfunction "Input_1") (pintype "passive"))
      (node (ref "C3_1") (pin "3") (pinfunction "Output_3") (pintype "passive"))
      (node (ref "C40_1") (pin "1") (pinfunction "1_1") (pintype "passive"))
      (node (ref "C41_1") (pin "1") (pinfunction "1_1") (pintype "passive"))
      (node (ref "C42_1") (pin "1") (pinfunction "Input_1") (pintype "passive"))
      (node (ref "C42_1") (pin "3") (pinfunction "Output_3") (pintype "passive"))
      (node (ref "C43_1") (pin "1") (pinfunction "C_1") (pintype "passive"))
      (node (ref "C44_1") (pin "1") (pinfunction "1_1") (pintype "passive"))
      (node (ref "C45_1") (pin "1") (pinfunction "1_1") (pintype "passive"))
      (node (ref "C46_1") (pin "1") (pinfunction "Input_1") (pintype "passive"))
      (node (ref "C46_1") (pin "3") (pinfunction "Output_3") (pintype "passive"))
      (node (ref "C47_1") (pin "1") (pinfunction "Input_1") (pintype "passive"))
      (node (ref "C47_1") (pin "3") (pinfunction "Output_3") (pintype "passive"))
      (node (ref "C48_1") (pin "1") (pinfunction "Input_1") (pintype "passive"))
      (node (ref "C48_1") (pin "3") (pinfunction "Output_3") (pintype "passive"))
      (node (ref "C49_1") (pin "1") (pinfunction "Input_1") (pintype "passive"))
      (node (ref "C49_1") (pin "3") (pinfunction "Output_3") (pintype "passive"))
      (node (ref "C4_1") (pin "1") (pinfunction "Input_1") (pintype "passive"))
      (node (ref "C4_1") (pin "3") (pinfunction "Output_3") (pintype "passive"))
      (node (ref "C50_1") (pin "1") (pinfunction "Input_1") (pintype "passive"))
      (node (ref "C50_1") (pin "3") (pinfunction "Output_3") (pintype "passive"))
      (node (ref "C51_1") (pin "1") (pinfunction "Input_1") (pintype "passive"))
      (node (ref "C51_1") (pin "3") (pinfunction "Output_3") (pintype "passive"))
      (node (ref "C52_1") (pin "1") (pinfunction "Input_1") (pintype "passive"))
      (node (ref "C52_1") (pin "3") (pinfunction "Output_3") (pintype "passive"))
      (node (ref "C53_1") (pin "1") (pinfunction "Input_1") (pintype "passive"))
      (node (ref "C53_1") (pin "3") (pinfunction "Output_3") (pintype "passive"))
      (node (ref "C54_1") (pin "1") (pinfunction "Input_1") (pintype "passive"))
      (node (ref "C54_1") (pin "3") (pinfunction "Output_3") (pintype "passive"))
      (node (ref "C55_1") (pin "2") (pinfunction "2_2") (pintype "passive"))
      (node (ref "C56_1") (pin "1") (pinfunction "Input_1") (pintype "passive"))
      (node (ref "C56_1") (pin "3") (pinfunction "Output_3") (pintype "passive"))
      (node (ref "C57_1") (pin "1") (pinfunction "Input_1") (pintype "passive"))
      (node (ref "C57_1") (pin "3") (pinfunction "Output_3") (pintype "passive"))
      (node (ref "C58_1") (pin "1") (pinfunction "Input_1") (pintype "passive"))
      (node (ref "C58_1") (pin "3") (pinfunction "Output_3") (pintype "passive"))
      (node (ref "C59_1") (pin "1") (pinfunction "Input_1") (pintype "passive"))
      (node (ref "C59_1") (pin "3") (pinfunction "Output_3") (pintype "passive"))
      (node (ref "C5_1") (pin "1") (pinfunction "Input_1") (pintype "passive"))
      (node (ref "C5_1") (pin "3") (pinfunction "Output_3") (pintype "passive"))
      (node (ref "C60_1") (pin "1") (pinfunction "Input_1") (pintype "passive"))
      (node (ref "C60_1") (pin "3") (pinfunction "Output_3") (pintype "passive"))
      (node (ref "C61_1") (pin "1") (pinfunction "Input_1") (pintype "passive"))
      (node (ref "C61_1") (pin "3") (pinfunction "Output_3") (pintype "passive"))
      (node (ref "C62_1") (pin "1") (pinfunction "Input_1") (pintype "passive"))
      (node (ref "C62_1") (pin "3") (pinfunction "Output_3") (pintype "passive"))
      (node (ref "C63_1") (pin "2") (pinfunction "2_2") (pintype "passive"))
      (node (ref "C64_1") (pin "1") (pinfunction "1_1") (pintype "passive"))
      (node (ref "C65_1") (pin "1") (pinfunction "1_1") (pintype "passive"))
      (node (ref "C66_1") (pin "1") (pinfunction "1_1") (pintype "passive"))
      (node (ref "C67_1") (pin "1") (pinfunction "Input_1") (pintype "passive"))
      (node (ref "C67_1") (pin "3") (pinfunction "Output_3") (pintype "passive"))
      (node (ref "C68_1") (pin "1") (pinfunction "Input_1") (pintype "passive"))
      (node (ref "C68_1") (pin "3") (pinfunction "Output_3") (pintype "passive"))
      (node (ref "C69_1") (pin "1") (pinfunction "Input_1") (pintype "passive"))
      (node (ref "C69_1") (pin "3") (pinfunction "Output_3") (pintype "passive"))
      (node (ref "C6_1") (pin "1") (pinfunction "Input_1") (pintype "passive"))
      (node (ref "C6_1") (pin "3") (pinfunction "Output_3") (pintype "passive"))
      (node (ref "C70_1") (pin "1") (pinfunction "Input_1") (pintype "passive"))
      (node (ref "C70_1") (pin "3") (pinfunction "Output_3") (pintype "passive"))
      (node (ref "C71_1") (pin "1") (pinfunction "Input_1") (pintype "passive"))
      (node (ref "C71_1") (pin "3") (pinfunction "Output_3") (pintype "passive"))
      (node (ref "C72_1") (pin "1") (pinfunction "Input_1") (pintype "passive"))
      (node (ref "C72_1") (pin "3") (pinfunction "Output_3") (pintype "passive"))
      (node (ref "C73_1") (pin "1") (pinfunction "Input_1") (pintype "passive"))
      (node (ref "C73_1") (pin "3") (pinfunction "Output_3") (pintype "passive"))
      (node (ref "C74_1") (pin "1") (pinfunction "Input_1") (pintype "passive"))
      (node (ref "C74_1") (pin "3") (pinfunction "Output_3") (pintype "passive"))
      (node (ref "C75_1") (pin "1") (pinfunction "Input_1") (pintype "passive"))
      (node (ref "C75_1") (pin "3") (pinfunction "Output_3") (pintype "passive"))
      (node (ref "C76_1") (pin "1") (pinfunction "Input_1") (pintype "passive"))
      (node (ref "C76_1") (pin "3") (pinfunction "Output_3") (pintype "passive"))
      (node (ref "C77_1") (pin "1") (pinfunction "Input_1") (pintype "passive"))
      (node (ref "C77_1") (pin "3") (pinfunction "Output_3") (pintype "passive"))
      (node (ref "C78_1") (pin "1") (pinfunction "Input_1") (pintype "passive"))
      (node (ref "C78_1") (pin "3") (pinfunction "Output_3") (pintype "passive"))
      (node (ref "C79_1") (pin "1") (pinfunction "C_1") (pintype "passive"))
      (node (ref "C7_1") (pin "1") (pinfunction "Input_1") (pintype "passive"))
      (node (ref "C7_1") (pin "3") (pinfunction "Output_3") (pintype "passive"))
      (node (ref "C80_1") (pin "2") (pinfunction "2_2") (pintype "passive"))
      (node (ref "C81_1") (pin "2") (pinfunction "2_2") (pintype "passive"))
      (node (ref "C82_1") (pin "1") (pinfunction "Input_1") (pintype "passive"))
      (node (ref "C82_1") (pin "3") (pinfunction "Output_3") (pintype "passive"))
      (node (ref "C83_1") (pin "1") (pinfunction "Input_1") (pintype "passive"))
      (node (ref "C83_1") (pin "3") (pinfunction "Output_3") (pintype "passive"))
      (node (ref "C84_1") (pin "1") (pinfunction "Input_1") (pintype "passive"))
      (node (ref "C84_1") (pin "3") (pinfunction "Output_3") (pintype "passive"))
      (node (ref "C85_1") (pin "2") (pinfunction "2_2") (pintype "passive"))
      (node (ref "C86_1") (pin "1") (pinfunction "Input_1") (pintype "passive"))
      (node (ref "C86_1") (pin "3") (pinfunction "Output_3") (pintype "passive"))
      (node (ref "C87_1") (pin "1") (pinfunction "Input_1") (pintype "passive"))
      (node (ref "C87_1") (pin "3") (pinfunction "Output_3") (pintype "passive"))
      (node (ref "C88_1") (pin "1") (pinfunction "Input_1") (pintype "passive"))
      (node (ref "C88_1") (pin "3") (pinfunction "Output_3") (pintype "passive"))
      (node (ref "C89_1") (pin "1") (pinfunction "Input_1") (pintype "passive"))
      (node (ref "C89_1") (pin "3") (pinfunction "Output_3") (pintype "passive"))
      (node (ref "C8_1") (pin "2") (pinfunction "2_2") (pintype "passive"))
      (node (ref "C90_1") (pin "1") (pinfunction "Input_1") (pintype "passive"))
      (node (ref "C90_1") (pin "3") (pinfunction "Output_3") (pintype "passive"))
      (node (ref "C91_1") (pin "1") (pinfunction "Input_1") (pintype "passive"))
      (node (ref "C91_1") (pin "3") (pinfunction "Output_3") (pintype "passive"))
      (node (ref "C92_1") (pin "1") (pinfunction "Input_1") (pintype "passive"))
      (node (ref "C92_1") (pin "3") (pinfunction "Output_3") (pintype "passive"))
      (node (ref "C93_1") (pin "1") (pinfunction "Input_1") (pintype "passive"))
      (node (ref "C93_1") (pin "3") (pinfunction "Output_3") (pintype "passive"))
      (node (ref "C94_1") (pin "2") (pinfunction "2_2") (pintype "passive"))
      (node (ref "C95_1") (pin "1") (pinfunction "Input_1") (pintype "passive"))
      (node (ref "C95_1") (pin "3") (pinfunction "Output_3") (pintype "passive"))
      (node (ref "C96_1") (pin "1") (pinfunction "Input_1") (pintype "passive"))
      (node (ref "C96_1") (pin "3") (pinfunction "Output_3") (pintype "passive"))
      (node (ref "C97_1") (pin "1") (pinfunction "Input_1") (pintype "passive"))
      (node (ref "C97_1") (pin "3") (pinfunction "Output_3") (pintype "passive"))
      (node (ref "C98_1") (pin "1") (pinfunction "Input_1") (pintype "passive"))
      (node (ref "C98_1") (pin "3") (pinfunction "Output_3") (pintype "passive"))
      (node (ref "C99_1") (pin "1") (pinfunction "Input_1") (pintype "passive"))
      (node (ref "C99_1") (pin "3") (pinfunction "Output_3") (pintype "passive"))
      (node (ref "C9_1") (pin "1") (pinfunction "1_1") (pintype "passive"))
      (node (ref "D1_1") (pin "2") (pinfunction "K2_2") (pintype "passive"))
      (node (ref "D2_1") (pin "2") (pinfunction "A2_2") (pintype "passive"))
      (node (ref "D3_1") (pin "2") (pinfunction "K2_2") (pintype "passive"))
      (node (ref "D4_1") (pin "2") (pinfunction "GND_2") (pintype "power_in"))
      (node (ref "D5_1") (pin "2") (pinfunction "A2_2") (pintype "passive"))
      (node (ref "D6_1") (pin "2") (pinfunction "K2_2") (pintype "passive"))
      (node (ref "D7_1") (pin "2") (pinfunction "A2_2") (pintype "passive"))
      (node (ref "J_ADC1_RST") (pin "3") (pinfunction "3_3") (pintype "passive"))
      (node (ref "J_GND5") (pin "1") (pinfunction "1_1") (pintype "passive"))
      (node (ref "J_GND6") (pin "1") (pinfunction "1_1") (pintype "passive"))
      (node (ref "LDO_AVDD1") (pin "11") (pinfunction "GND_11") (pintype "power_in"))
      (node (ref "LDO_AVDD1") (pin "12") (pinfunction "GND_12") (pintype "power_in"))
      (node (ref "LDO_AVDD1") (pin "19") (pinfunction "GND_19") (pintype "power_in"))
      (node (ref "LDO_AVDD2") (pin "1") (pinfunction "CLKDIS_1") (pintype "passive"))
      (node (ref "LDO_AVDD2") (pin "11") (pinfunction "AGND_11") (pintype "power_in"))
      (node (ref "LDO_AVDD2") (pin "19") (pinfunction "DGND_19") (pintype "power_in"))
      (node (ref "LDO_CVDD1") (pin "11") (pinfunction "GND_11") (pintype "power_in"))
      (node (ref "LDO_CVDD1") (pin "12") (pinfunction "GND_12") (pintype "power_in"))
      (node (ref "LDO_CVDD1") (pin "19") (pinfunction "GND_19") (pintype "power_in"))
      (node (ref "LDO_CVDD1") (pin "3") (pinfunction "VO1_3") (pintype "tri_state"))
      (node (ref "LDO_CVDD2") (pin "1") (pinfunction "CLKDIS_1") (pintype "passive"))
      (node (ref "LDO_CVDD2") (pin "11") (pinfunction "AGND_11") (pintype "power_in"))
      (node (ref "LDO_CVDD2") (pin "19") (pinfunction "DGND_19") (pintype "power_in"))
      (node (ref "LDO_DVDD1") (pin "11") (pinfunction "GND_11") (pintype "power_in"))
      (node (ref "LDO_DVDD1") (pin "12") (pinfunction "GND_12") (pintype "power_in"))
      (node (ref "LDO_DVDD1") (pin "19") (pinfunction "GND_19") (pintype "power_in"))
      (node (ref "LDO_DVDD1") (pin "3") (pinfunction "VO1_3") (pintype "tri_state"))
      (node (ref "LDO_DVDD2") (pin "1") (pinfunction "CLKDIS_1") (pintype "passive"))
      (node (ref "LDO_DVDD2") (pin "11") (pinfunction "AGND_11") (pintype "power_in"))
      (node (ref "LDO_DVDD2") (pin "19") (pinfunction "DGND_19") (pintype "power_in"))
      (node (ref "R19_1") (pin "1") (pinfunction "1_1") (pintype "passive"))
      (node (ref "R20_1") (pin "1") (pinfunction "1_1") (pintype "passive"))
      (node (ref "R22_1") (pin "1") (pinfunction "1_1") (pintype "passive"))
      (node (ref "R27_1") (pin "1") (pinfunction "1_1") (pintype "passive"))
      (node (ref "R28_1") (pin "1") (pinfunction "1_1") (pintype "passive"))
      (node (ref "R30_1") (pin "1") (pinfunction "1_1") (pintype "passive"))
      (node (ref "R34_1") (pin "1") (pinfunction "1_1") (pintype "passive"))
      (node (ref "R36_1") (pin "1") (pinfunction "1_1") (pintype "passive"))
      (node (ref "R38_1") (pin "1") (pinfunction "1_1") (pintype "passive"))
      (node (ref "R39_1") (pin "1") (pinfunction "1_1") (pintype "passive"))
      (node (ref "R6_1") (pin "1") (pinfunction "1_1") (pintype "passive"))
      (node (ref "R7_1") (pin "1") (pinfunction "1_1") (pintype "passive"))
      (node (ref "R9_1") (pin "1") (pinfunction "1_1") (pintype "passive"))
      (node (ref "U_AVDD_POT") (pin "3") (pinfunction "GND_3") (pintype "power_in"))
      (node (ref "U_AVDD_POT") (pin "7") (pinfunction "B_7") (pintype "passive"))
      (node (ref "U_CVDD_POT") (pin "3") (pinfunction "GND_3") (pintype "power_in"))
      (node (ref "U_CVDD_POT") (pin "6") (pinfunction "AD0_6") (pintype "bidirectional"))
      (node (ref "U_CVDD_POT") (pin "7") (pinfunction "B_7") (pintype "passive"))
      (node (ref "U_DVDD_POT") (pin "1") (pinfunction "HVC/A0_1") (pintype "input"))
      (node (ref "U_DVDD_POT") (pin "4") (pinfunction "VSS_4") (pintype "power_in"))
      (node (ref "U_DVDD_POT") (pin "7") (pinfunction "P0B_7") (pintype "passive"))
    )
    (net (code "37") (name "Net-(ADC_1-~{DRDY})") (class "Default")
      (node (ref "ADC_1") (pin "14") (pinfunction "~{DRDY}_14") (pintype "output"))
      (node (ref "R16_1") (pin "1") (pinfunction "1_1") (pintype "passive"))
    )
    (net (code "38") (name "Net-(ADC_1-~{RESET})") (class "Default")
      (node (ref "ADC_1") (pin "3") (pinfunction "~{RESET}_3") (pintype "input"))
      (node (ref "D4_1") (pin "1") (pinfunction "I/O_1") (pintype "passive"))
      (node (ref "J_ADC1_RST") (pin "2") (pinfunction "2_2") (pintype "passive"))
    )
    (net (code "39") (name "Net-(LDO_AVDD1-BIASF)") (class "Default")
      (node (ref "C20_1") (pin "2") (pinfunction "2_2") (pintype "passive"))
      (node (ref "LDO_AVDD1") (pin "16") (pinfunction "BIASF_16") (pintype "power_in"))
    )
    (net (code "40") (name "Net-(LDO_AVDD1-IMON)") (class "Default")
      (node (ref "LDO_AVDD1") (pin "15") (pinfunction "IMON_15") (pintype "output"))
      (node (ref "R6_1") (pin "2") (pinfunction "2_2") (pintype "passive"))
    )
    (net (code "41") (name "Net-(LDO_AVDD1-REF)") (class "Default")
      (node (ref "C19_1") (pin "2") (pinfunction "2_2") (pintype "passive"))
      (node (ref "LDO_AVDD1") (pin "13") (pinfunction "REF_13") (pintype "passive"))
    )
    (net (code "42") (name "Net-(LDO_AVDD1-VO0)") (class "Default")
      (node (ref "LDO_AVDD1") (pin "2") (pinfunction "VO0_2") (pintype "tri_state"))
      (node (ref "R33_1") (pin "1") (pinfunction "1_1") (pintype "passive"))
      (node (ref "R34_1") (pin "2") (pinfunction "2_2") (pintype "passive"))
    )
    (net (code "43") (name "Net-(LDO_AVDD1-VO1)") (class "Default")
      (node (ref "LDO_AVDD1") (pin "3") (pinfunction "VO1_3") (pintype "tri_state"))
      (node (ref "R39_1") (pin "2") (pinfunction "2_2") (pintype "passive"))
    )
    (net (code "44") (name "Net-(LDO_AVDD2-BIASDF)") (class "Default")
      (node (ref "C10_1") (pin "2") (pinfunction "2_2") (pintype "passive"))
      (node (ref "LDO_AVDD2") (pin "18") (pinfunction "BIASDF_18") (pintype "passive"))
    )
    (net (code "45") (name "Net-(LDO_AVDD2-PG)") (class "Default")
      (node (ref "LDO_AVDD2") (pin "6") (pinfunction "PG_6") (pintype "output"))
      (node (ref "R1_1") (pin "1") (pinfunction "1_1") (pintype "passive"))
    )
    (net (code "46") (name "Net-(LDO_AVDD2-PGFB)") (class "Default")
      (node (ref "LDO_AVDD2") (pin "7") (pinfunction "PGFB_7") (pintype "passive"))
      (node (ref "R5_1") (pin "1") (pinfunction "1_1") (pintype "passive"))
      (node (ref "R7_1") (pin "2") (pinfunction "2_2") (pintype "passive"))
    )
    (net (code "47") (name "Net-(LDO_AVDD2-SETCAP)") (class "Default")
      (node (ref "C11_1") (pin "2") (pinfunction "2_2") (pintype "passive"))
      (node (ref "LDO_AVDD2") (pin "12") (pinfunction "SETCAP_12") (pintype "passive"))
    )
    (net (code "48") (name "Net-(LDO_AVDD2-SETRES)") (class "Default")
      (node (ref "LDO_AVDD2") (pin "13") (pinfunction "SETRES_13") (pintype "passive"))
      (node (ref "R12_1") (pin "2") (pinfunction "2_2") (pintype "passive"))
    )
    (net (code "49") (name "Net-(LDO_CVDD1-BIASF)") (class "Default")
      (node (ref "C45_1") (pin "2") (pinfunction "2_2") (pintype "passive"))
      (node (ref "LDO_CVDD1") (pin "16") (pinfunction "BIASF_16") (pintype "power_in"))
    )
    (net (code "50") (name "Net-(LDO_CVDD1-IMON)") (class "Default")
      (node (ref "LDO_CVDD1") (pin "15") (pinfunction "IMON_15") (pintype "output"))
      (node (ref "R19_1") (pin "2") (pinfunction "2_2") (pintype "passive"))
    )
    (net (code "51") (name "Net-(LDO_CVDD1-REF)") (class "Default")
      (node (ref "C44_1") (pin "2") (pinfunction "2_2") (pintype "passive"))
      (node (ref "LDO_CVDD1") (pin "13") (pinfunction "REF_13") (pintype "passive"))
    )
    (net (code "52") (name "Net-(LDO_CVDD1-VO0)") (class "Default")
      (node (ref "LDO_CVDD1") (pin "2") (pinfunction "VO0_2") (pintype "tri_state"))
      (node (ref "R35_1") (pin "1") (pinfunction "1_1") (pintype "passive"))
      (node (ref "R36_1") (pin "2") (pinfunction "2_2") (pintype "passive"))
    )
    (net (code "53") (name "Net-(LDO_CVDD2-BIASDF)") (class "Default")
      (node (ref "C40_1") (pin "2") (pinfunction "2_2") (pintype "passive"))
      (node (ref "LDO_CVDD2") (pin "18") (pinfunction "BIASDF_18") (pintype "passive"))
    )
    (net (code "54") (name "Net-(LDO_CVDD2-PG)") (class "Default")
      (node (ref "LDO_CVDD2") (pin "6") (pinfunction "PG_6") (pintype "output"))
      (node (ref "R17_1") (pin "1") (pinfunction "1_1") (pintype "passive"))
    )
    (net (code "55") (name "Net-(LDO_CVDD2-PGFB)") (class "Default")
      (node (ref "LDO_CVDD2") (pin "7") (pinfunction "PGFB_7") (pintype "passive"))
      (node (ref "R18_1") (pin "1") (pinfunction "1_1") (pintype "passive"))
      (node (ref "R20_1") (pin "2") (pinfunction "2_2") (pintype "passive"))
    )
    (net (code "56") (name "Net-(LDO_CVDD2-SETCAP)") (class "Default")
      (node (ref "C41_1") (pin "2") (pinfunction "2_2") (pintype "passive"))
      (node (ref "LDO_CVDD2") (pin "12") (pinfunction "SETCAP_12") (pintype "passive"))
    )
    (net (code "57") (name "Net-(LDO_CVDD2-SETRES)") (class "Default")
      (node (ref "LDO_CVDD2") (pin "13") (pinfunction "SETRES_13") (pintype "passive"))
      (node (ref "R23_1") (pin "1") (pinfunction "1_1") (pintype "passive"))
    )
    (net (code "58") (name "Net-(LDO_DVDD1-BIASF)") (class "Default")
      (node (ref "C81_1") (pin "1") (pinfunction "1_1") (pintype "passive"))
      (node (ref "LDO_DVDD1") (pin "16") (pinfunction "BIASF_16") (pintype "power_in"))
    )
    (net (code "59") (name "Net-(LDO_DVDD1-IMON)") (class "Default")
      (node (ref "LDO_DVDD1") (pin "15") (pinfunction "IMON_15") (pintype "output"))
      (node (ref "R28_1") (pin "2") (pinfunction "2_2") (pintype "passive"))
    )
    (net (code "60") (name "Net-(LDO_DVDD1-REF)") (class "Default")
      (node (ref "C80_1") (pin "1") (pinfunction "1_1") (pintype "passive"))
      (node (ref "LDO_DVDD1") (pin "13") (pinfunction "REF_13") (pintype "passive"))
    )
    (net (code "61") (name "Net-(LDO_DVDD1-VO0)") (class "Default")
      (node (ref "LDO_DVDD1") (pin "2") (pinfunction "VO0_2") (pintype "tri_state"))
      (node (ref "R37_1") (pin "1") (pinfunction "1_1") (pintype "passive"))
      (node (ref "R38_1") (pin "2") (pinfunction "2_2") (pintype "passive"))
    )
    (net (code "62") (name "Net-(LDO_DVDD2-BIASDF)") (class "Default")
      (node (ref "C65_1") (pin "2") (pinfunction "2_2") (pintype "passive"))
      (node (ref "LDO_DVDD2") (pin "18") (pinfunction "BIASDF_18") (pintype "passive"))
    )
    (net (code "63") (name "Net-(LDO_DVDD2-PG)") (class "Default")
      (node (ref "LDO_DVDD2") (pin "6") (pinfunction "PG_6") (pintype "output"))
      (node (ref "R25_1") (pin "1") (pinfunction "1_1") (pintype "passive"))
    )
    (net (code "64") (name "Net-(LDO_DVDD2-PGFB)") (class "Default")
      (node (ref "LDO_DVDD2") (pin "7") (pinfunction "PGFB_7") (pintype "passive"))
      (node (ref "R26_1") (pin "1") (pinfunction "1_1") (pintype "passive"))
      (node (ref "R27_1") (pin "2") (pinfunction "2_2") (pintype "passive"))
    )
    (net (code "65") (name "Net-(LDO_DVDD2-SETCAP)") (class "Default")
      (node (ref "C66_1") (pin "2") (pinfunction "2_2") (pintype "passive"))
      (node (ref "LDO_DVDD2") (pin "12") (pinfunction "SETCAP_12") (pintype "passive"))
    )
    (net (code "66") (name "Net-(LDO_DVDD2-SETRES)") (class "Default")
      (node (ref "LDO_DVDD2") (pin "13") (pinfunction "SETRES_13") (pintype "passive"))
      (node (ref "R31_1") (pin "2") (pinfunction "2_2") (pintype "passive"))
    )
    (net (code "67") (name "Net-(U_AVDD_IMON--IN)") (class "Default")
      (node (ref "R13_1") (pin "2") (pinfunction "2_2") (pintype "passive"))
      (node (ref "U_AVDD_IMON") (pin "1") (pinfunction "OUT_1") (pintype "passive"))
      (node (ref "U_AVDD_IMON") (pin "4") (pinfunction "-IN_4") (pintype "tri_state"))
    )
    (net (code "68") (name "Net-(U_AVDD_POT-A)") (class "Default")
      (node (ref "R12_1") (pin "1") (pinfunction "1_1") (pintype "passive"))
      (node (ref "U_AVDD_POT") (pin "1") (pinfunction "W_1") (pintype "passive"))
      (node (ref "U_AVDD_POT") (pin "8") (pinfunction "A_8") (pintype "passive"))
    )
    (net (code "69") (name "Net-(U_CVDD_IMON--IN)") (class "Default")
      (node (ref "R24_1") (pin "2") (pinfunction "2_2") (pintype "passive"))
      (node (ref "U_CVDD_IMON") (pin "1") (pinfunction "OUT_1") (pintype "passive"))
      (node (ref "U_CVDD_IMON") (pin "4") (pinfunction "-IN_4") (pintype "tri_state"))
    )
    (net (code "70") (name "Net-(U_CVDD_POT-A)") (class "Default")
      (node (ref "R23_1") (pin "2") (pinfunction "2_2") (pintype "passive"))
      (node (ref "U_CVDD_POT") (pin "1") (pinfunction "W_1") (pintype "passive"))
      (node (ref "U_CVDD_POT") (pin "8") (pinfunction "A_8") (pintype "passive"))
    )
    (net (code "71") (name "Net-(U_DVDD_IMON--IN)") (class "Default")
      (node (ref "R32_1") (pin "2") (pinfunction "2_2") (pintype "passive"))
      (node (ref "U_DVDD_IMON") (pin "1") (pinfunction "OUT_1") (pintype "passive"))
      (node (ref "U_DVDD_IMON") (pin "4") (pinfunction "-IN_4") (pintype "tri_state"))
    )
    (net (code "72") (name "Net-(U_DVDD_POT-P0A)") (class "Default")
      (node (ref "R31_1") (pin "1") (pinfunction "1_1") (pintype "passive"))
      (node (ref "U_DVDD_POT") (pin "5") (pinfunction "P0A_5") (pintype "passive"))
      (node (ref "U_DVDD_POT") (pin "6") (pinfunction "P0W_6") (pintype "passive"))
    )
    (net (code "73") (name "XAVDD_N2V5") (class "Default")
      (node (ref "ADC_1") (pin "5") (pinfunction "AVSS_5") (pintype "power_in"))
      (node (ref "C26_1") (pin "2") (pinfunction "GND_2") (pintype "passive"))
      (node (ref "C42_1") (pin "2") (pinfunction "GND_2") (pintype "passive"))
      (node (ref "C54_1") (pin "2") (pinfunction "GND_2") (pintype "passive"))
      (node (ref "C84_1") (pin "2") (pinfunction "GND_2") (pintype "passive"))
      (node (ref "U_AVDD_IMON") (pin "2") (pinfunction "V-_2") (pintype "power_in"))
      (node (ref "U_CVDD_IMON") (pin "2") (pinfunction "V-_2") (pintype "power_in"))
      (node (ref "U_DVDD_IMON") (pin "2") (pinfunction "V-_2") (pintype "power_in"))
    )
    (net (code "74") (name "XAVDD_P2V5") (class "Default")
      (node (ref "ADC_1") (pin "12") (pinfunction "AVDD_12") (pintype "power_in"))
      (node (ref "ADC_1") (pin "13") (pinfunction "DVDD_13") (pintype "power_in"))
      (node (ref "ADC_1") (pin "9") (pinfunction "REFP_9") (pintype "passive"))
      (node (ref "C25_1") (pin "2") (pinfunction "GND_2") (pintype "passive"))
      (node (ref "C28_1") (pin "2") (pinfunction "GND_2") (pintype "passive"))
      (node (ref "C53_1") (pin "2") (pinfunction "GND_2") (pintype "passive"))
      (node (ref "U_AVDD_IMON") (pin "5") (pinfunction "V+_5") (pintype "power_in"))
      (node (ref "U_CVDD_IMON") (pin "5") (pinfunction "V+_5") (pintype "power_in"))
      (node (ref "U_DVDD_IMON") (pin "5") (pinfunction "V+_5") (pintype "power_in"))
    )
    (net (code "75") (name "XDVDD_P2V5") (class "Default")
      (node (ref "ADC_1") (pin "1") (pinfunction "A0_1") (pintype "input"))
      (node (ref "ADC_1") (pin "2") (pinfunction "A1_2") (pintype "input"))
      (node (ref "C29_1") (pin "1") (pinfunction "1_1") (pintype "passive"))
      (node (ref "C30_1") (pin "1") (pinfunction "1_1") (pintype "passive"))
      (node (ref "J_ADC1_RST") (pin "1") (pinfunction "1_1") (pintype "passive"))
      (node (ref "R14_1") (pin "2") (pinfunction "2_2") (pintype "passive"))
      (node (ref "R15_1") (pin "2") (pinfunction "2_2") (pintype "passive"))
      (node (ref "R16_1") (pin "2") (pinfunction "2_2") (pintype "passive"))
    )
    (net (code "76") (name "XDVDD_P3V3") (class "Default")
      (node (ref "C31_1") (pin "1") (pinfunction "1_1") (pintype "passive"))
      (node (ref "C38_1") (pin "1") (pinfunction "1_1") (pintype "passive"))
      (node (ref "C56_1") (pin "2") (pinfunction "GND_2") (pintype "passive"))
      (node (ref "C5_1") (pin "2") (pinfunction "GND_2") (pintype "passive"))
      (node (ref "C63_1") (pin "1") (pinfunction "1_1") (pintype "passive"))
      (node (ref "C8_1") (pin "1") (pinfunction "1_1") (pintype "passive"))
      (node (ref "C94_1") (pin "1") (pinfunction "1_1") (pintype "passive"))
      (node (ref "LDO_AVDD1") (pin "1") (pinfunction "EN_1") (pintype "input"))
      (node (ref "LDO_AVDD1") (pin "14") (pinfunction "MARG_14") (pintype "passive"))
      (node (ref "LDO_AVDD1") (pin "17") (pinfunction "BIAS_17") (pintype "power_in"))
      (node (ref "LDO_AVDD1") (pin "4") (pinfunction "VO2_4") (pintype "tri_state"))
      (node (ref "LDO_AVDD2") (pin "17") (pinfunction "BIAS_17") (pintype "power_in"))
      (node (ref "LDO_CVDD1") (pin "1") (pinfunction "EN_1") (pintype "input"))
      (node (ref "LDO_CVDD1") (pin "14") (pinfunction "MARG_14") (pintype "passive"))
      (node (ref "LDO_CVDD1") (pin "17") (pinfunction "BIAS_17") (pintype "power_in"))
      (node (ref "LDO_CVDD1") (pin "4") (pinfunction "VO2_4") (pintype "tri_state"))
      (node (ref "LDO_CVDD2") (pin "17") (pinfunction "BIAS_17") (pintype "power_in"))
      (node (ref "LDO_DVDD1") (pin "1") (pinfunction "EN_1") (pintype "input"))
      (node (ref "LDO_DVDD1") (pin "14") (pinfunction "MARG_14") (pintype "passive"))
      (node (ref "LDO_DVDD1") (pin "17") (pinfunction "BIAS_17") (pintype "power_in"))
      (node (ref "LDO_DVDD1") (pin "4") (pinfunction "VO2_4") (pintype "tri_state"))
      (node (ref "LDO_DVDD2") (pin "17") (pinfunction "BIAS_17") (pintype "power_in"))
      (node (ref "R10_1") (pin "2") (pinfunction "2_2") (pintype "passive"))
      (node (ref "R11_1") (pin "2") (pinfunction "2_2") (pintype "passive"))
      (node (ref "R17_1") (pin "2") (pinfunction "2_2") (pintype "passive"))
      (node (ref "R1_1") (pin "2") (pinfunction "2_2") (pintype "passive"))
      (node (ref "R25_1") (pin "2") (pinfunction "2_2") (pintype "passive"))
      (node (ref "R2_1") (pin "2") (pinfunction "2_2") (pintype "passive"))
      (node (ref "R33_1") (pin "2") (pinfunction "2_2") (pintype "passive"))
      (node (ref "R35_1") (pin "2") (pinfunction "2_2") (pintype "passive"))
      (node (ref "R37_1") (pin "2") (pinfunction "2_2") (pintype "passive"))
      (node (ref "R3_1") (pin "2") (pinfunction "2_2") (pintype "passive"))
      (node (ref "R4_1") (pin "2") (pinfunction "2_2") (pintype "passive"))
      (node (ref "U_AVDD_POT") (pin "2") (pinfunction "VDD_2") (pintype "power_in"))
      (node (ref "U_AVDD_POT") (pin "6") (pinfunction "AD0_6") (pintype "bidirectional"))
      (node (ref "U_CVDD_POT") (pin "2") (pinfunction "VDD_2") (pintype "power_in"))
      (node (ref "U_DVDD_POT") (pin "8") (pinfunction "VDD_8") (pintype "power_in"))
    )
    (net (code "77") (name "unconnected-(LDO_AVDD1-PG-Pad5)") (class "Default")
      (node (ref "LDO_AVDD1") (pin "5") (pinfunction "PG_5") (pintype "output+no_connect"))
    )
    (net (code "78") (name "unconnected-(LDO_AVDD1-TEMP-Pad18)") (class "Default")
      (node (ref "LDO_AVDD1") (pin "18") (pinfunction "TEMP_18") (pintype "output+no_connect"))
    )
    (net (code "79") (name "unconnected-(LDO_AVDD1-VIOC-Pad6)") (class "Default")
      (node (ref "LDO_AVDD1") (pin "6") (pinfunction "VIOC_6") (pintype "power_in+no_connect"))
    )
    (net (code "80") (name "unconnected-(LDO_CVDD1-PG-Pad5)") (class "Default")
      (node (ref "LDO_CVDD1") (pin "5") (pinfunction "PG_5") (pintype "output+no_connect"))
    )
    (net (code "81") (name "unconnected-(LDO_CVDD1-TEMP-Pad18)") (class "Default")
      (node (ref "LDO_CVDD1") (pin "18") (pinfunction "TEMP_18") (pintype "output+no_connect"))
    )
    (net (code "82") (name "unconnected-(LDO_CVDD1-VIOC-Pad6)") (class "Default")
      (node (ref "LDO_CVDD1") (pin "6") (pinfunction "VIOC_6") (pintype "power_in+no_connect"))
    )
    (net (code "83") (name "unconnected-(LDO_DVDD1-PG-Pad5)") (class "Default")
      (node (ref "LDO_DVDD1") (pin "5") (pinfunction "PG_5") (pintype "output+no_connect"))
    )
    (net (code "84") (name "unconnected-(LDO_DVDD1-TEMP-Pad18)") (class "Default")
      (node (ref "LDO_DVDD1") (pin "18") (pinfunction "TEMP_18") (pintype "output+no_connect"))
    )
    (net (code "85") (name "unconnected-(LDO_DVDD1-VIOC-Pad6)") (class "Default")
      (node (ref "LDO_DVDD1") (pin "6") (pinfunction "VIOC_6") (pintype "power_in+no_connect"))
    )
  )
)
